# 0831.net
KiCad netlist of a schematic drawn in Altium Designer
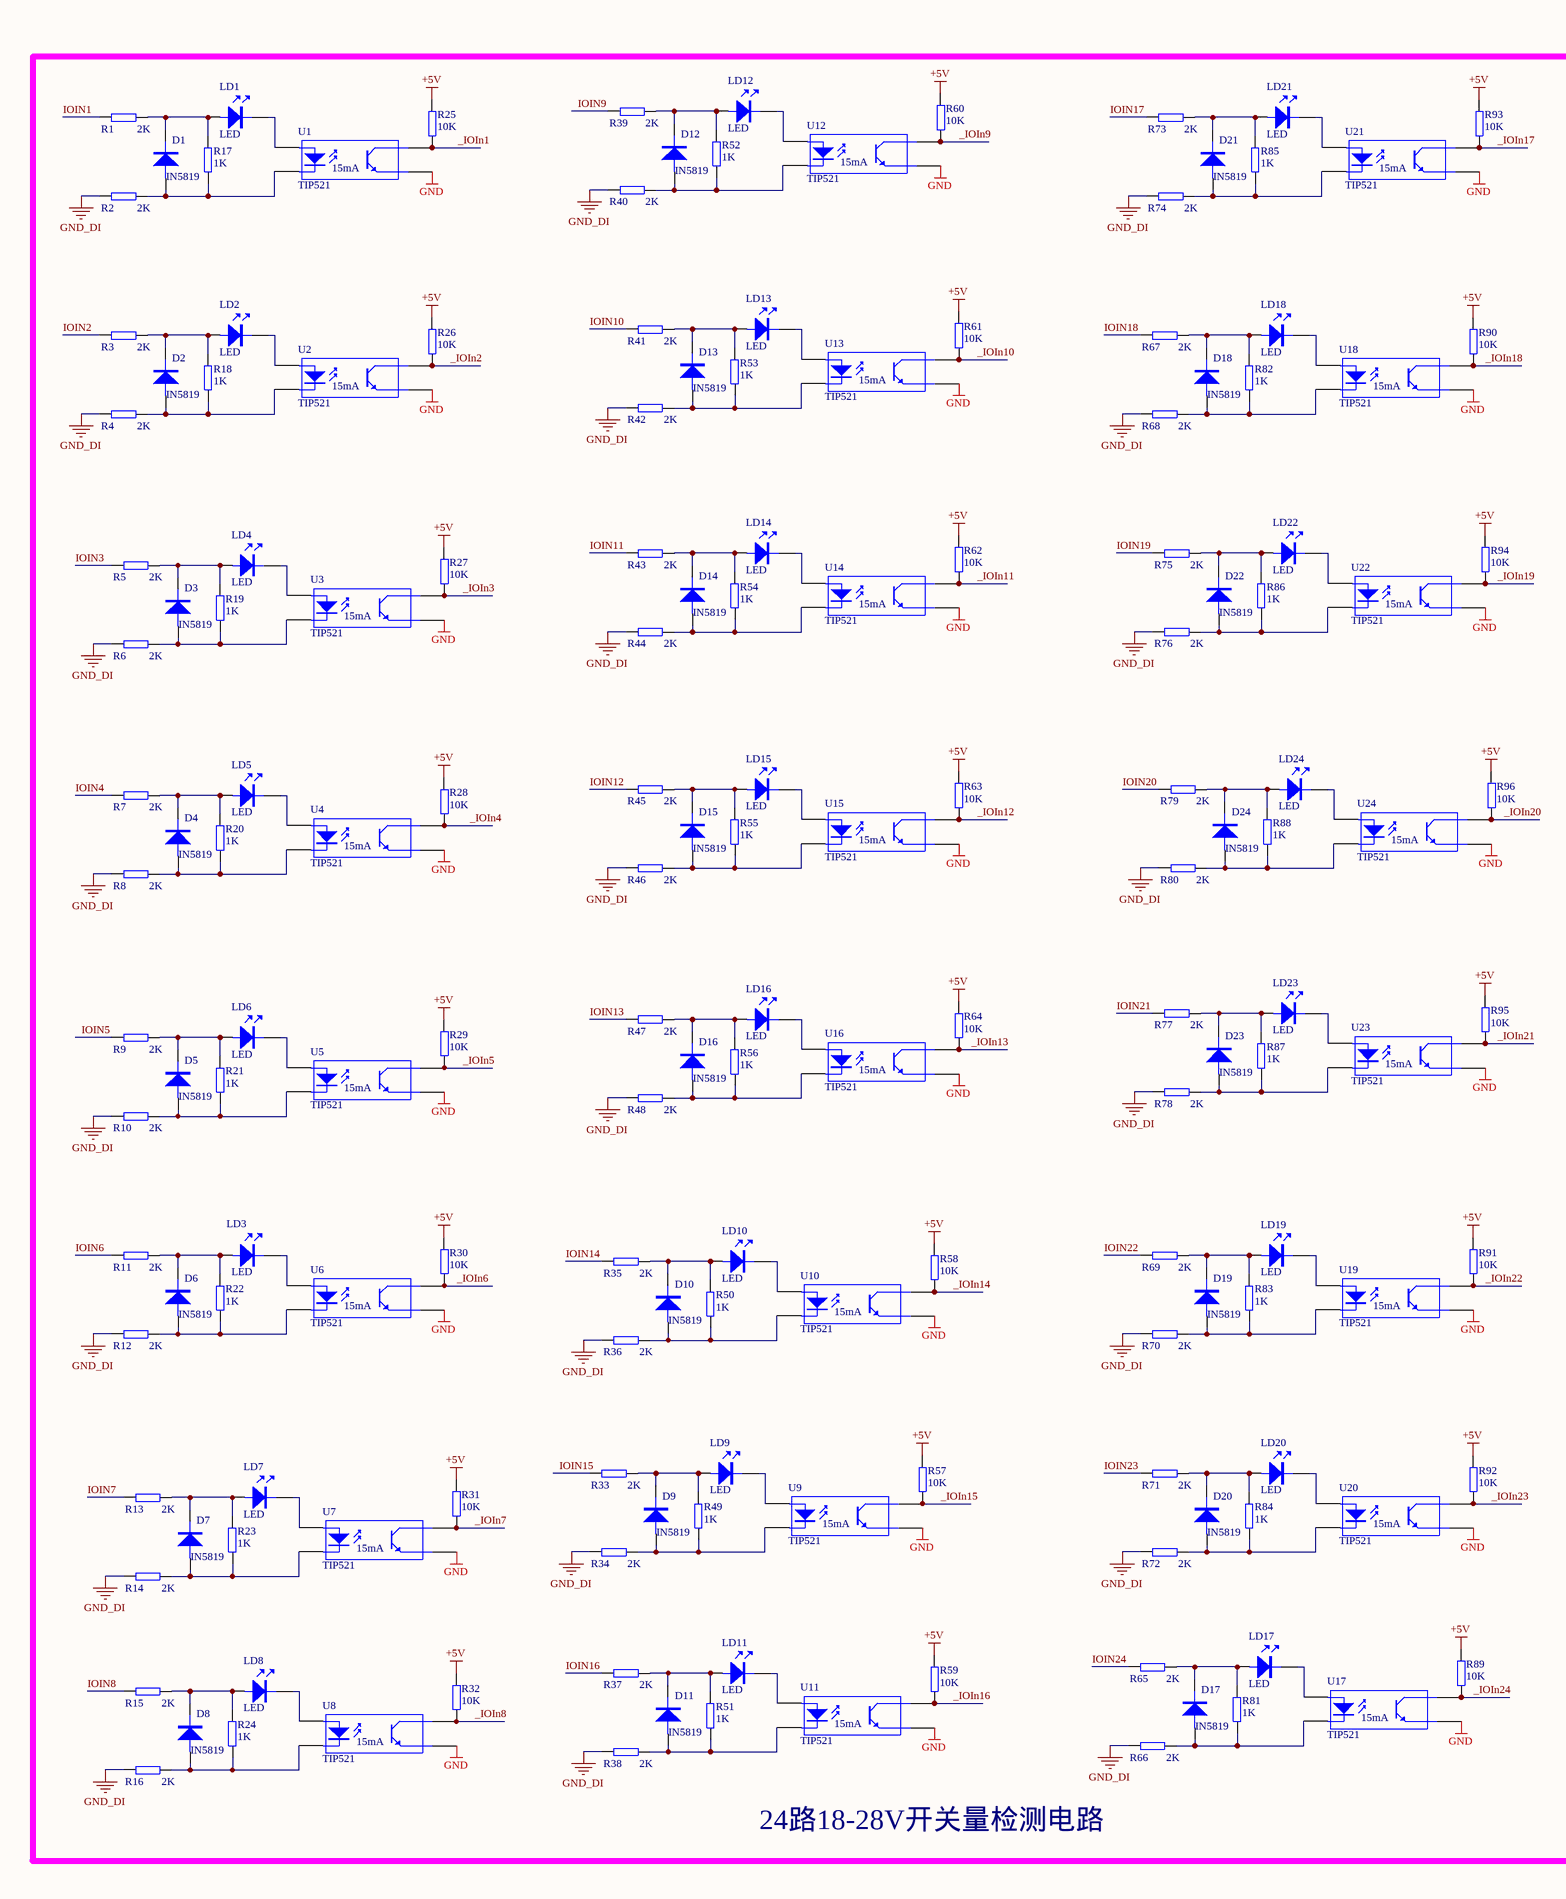
[diagram p0: 如意硬件采集模块0831.SchDoc, left]
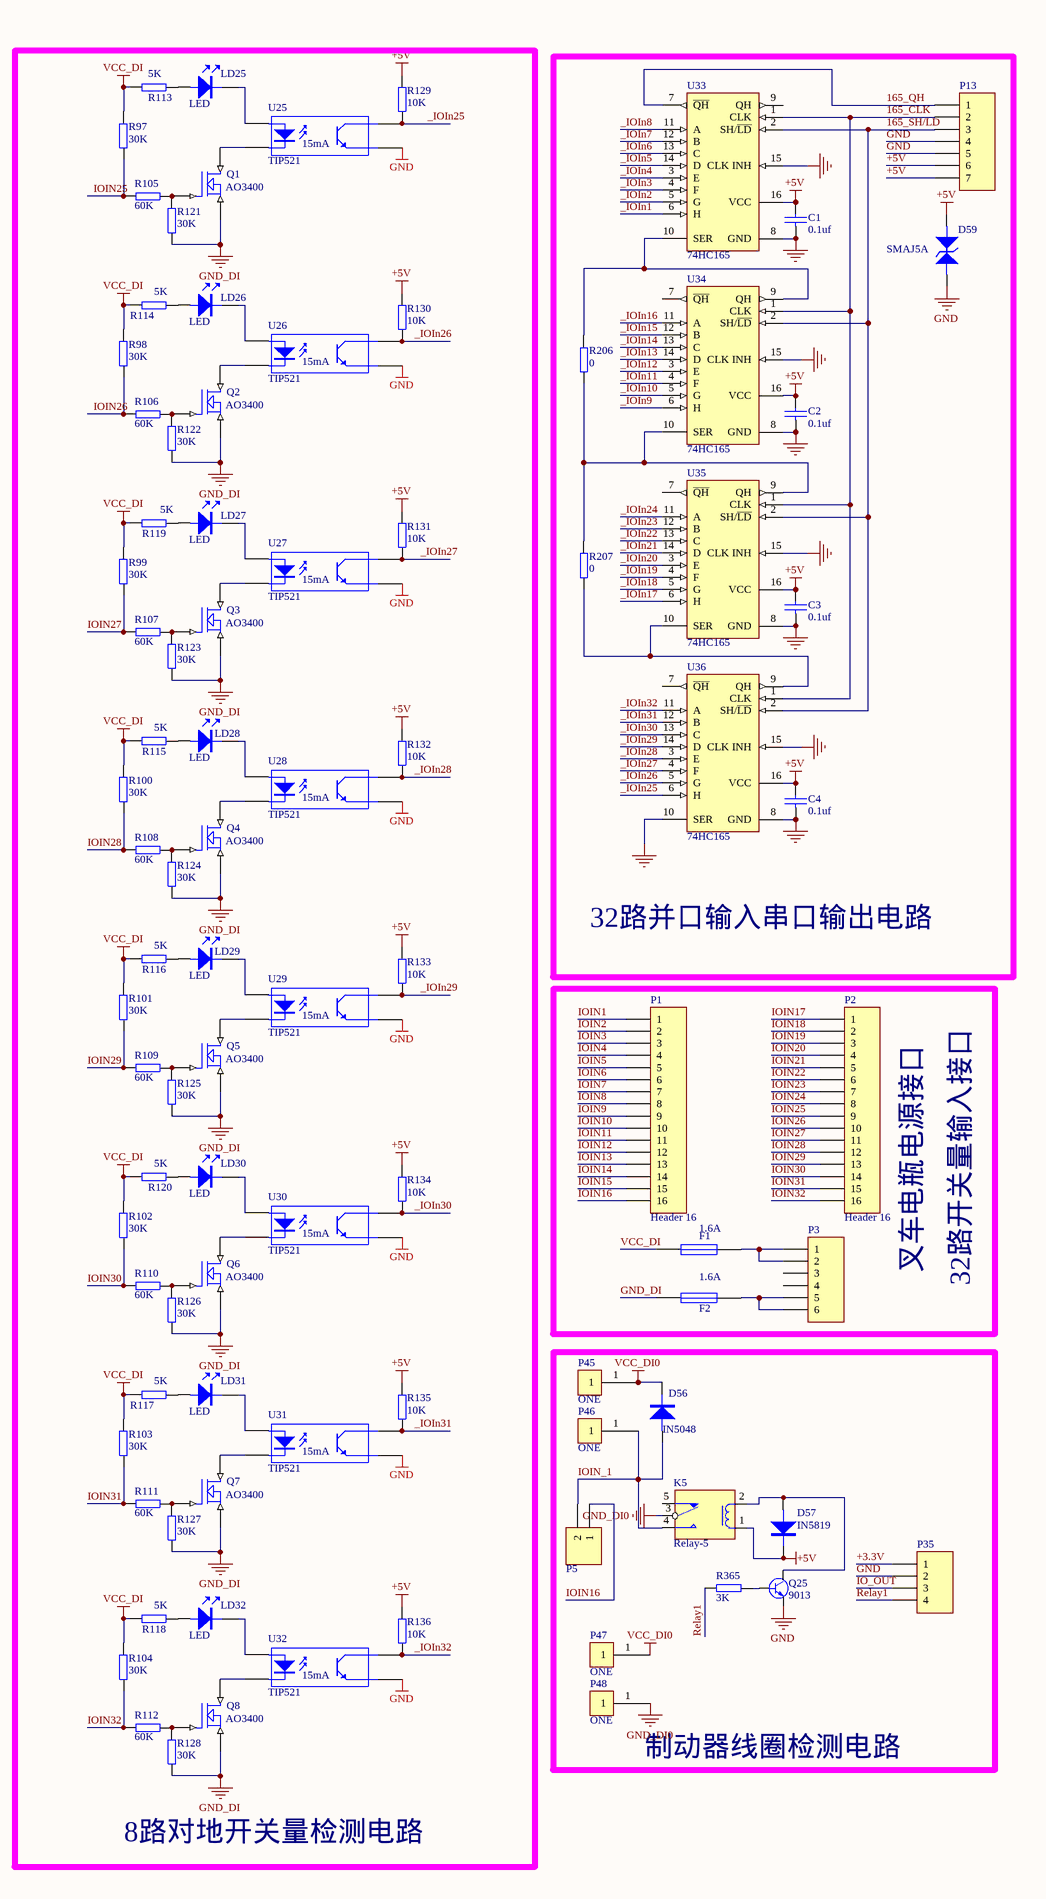
[diagram p1: 如意硬件采集模块0831.SchDoc, right]

(export (version "E")
  (design (tool "Eeschema 10.0.6"))
  (components
    (comp (ref "C1")
      (value "0.1uf")
      (footprint "0603C-1")
      (description "Capacitor")
      (libsource (lib "*") (part "CAP"))
    )
    (comp (ref "C2")
      (value "0.1uf")
      (footprint "0603C-1")
      (description "Capacitor")
      (libsource (lib "*") (part "CAP"))
    )
    (comp (ref "C3")
      (value "0.1uf")
      (footprint "0603C-1")
      (description "Capacitor")
      (libsource (lib "*") (part "CAP"))
    )
    (comp (ref "C4")
      (value "0.1uf")
      (footprint "0603C-1")
      (description "Capacitor")
      (libsource (lib "*") (part "CAP"))
    )
    (comp (ref "D1")
      (value "IN5819")
      (footprint "DIODETP-5")
      (description "Diode")
      (libsource (lib "*") (part "DIODE"))
    )
    (comp (ref "D2")
      (value "IN5819")
      (footprint "DIODETP-5")
      (description "Diode")
      (libsource (lib "*") (part "DIODE"))
    )
    (comp (ref "D3")
      (value "IN5819")
      (footprint "DIODETP-5")
      (description "Diode")
      (libsource (lib "*") (part "DIODE"))
    )
    (comp (ref "D4")
      (value "IN5819")
      (footprint "DIODETP-5")
      (description "Diode")
      (libsource (lib "*") (part "DIODE"))
    )
    (comp (ref "D5")
      (value "IN5819")
      (footprint "DIODETP-5")
      (description "Diode")
      (libsource (lib "*") (part "DIODE"))
    )
    (comp (ref "D6")
      (value "IN5819")
      (footprint "DIODETP-5")
      (description "Diode")
      (libsource (lib "*") (part "DIODE"))
    )
    (comp (ref "D7")
      (value "IN5819")
      (footprint "DIODETP-5")
      (description "Diode")
      (libsource (lib "*") (part "DIODE"))
    )
    (comp (ref "D8")
      (value "IN5819")
      (footprint "DIODETP-5")
      (description "Diode")
      (libsource (lib "*") (part "DIODE"))
    )
    (comp (ref "D9")
      (value "IN5819")
      (footprint "DIODETP-5")
      (description "Diode")
      (libsource (lib "*") (part "DIODE"))
    )
    (comp (ref "D10")
      (value "IN5819")
      (footprint "DIODETP-5")
      (description "Diode")
      (libsource (lib "*") (part "DIODE"))
    )
    (comp (ref "D11")
      (value "IN5819")
      (footprint "DIODETP-5")
      (description "Diode")
      (libsource (lib "*") (part "DIODE"))
    )
    (comp (ref "D12")
      (value "IN5819")
      (footprint "DIODETP-5")
      (description "Diode")
      (libsource (lib "*") (part "DIODE"))
    )
    (comp (ref "D13")
      (value "IN5819")
      (footprint "DIODETP-5")
      (description "Diode")
      (libsource (lib "*") (part "DIODE"))
    )
    (comp (ref "D14")
      (value "IN5819")
      (footprint "DIODETP-5")
      (description "Diode")
      (libsource (lib "*") (part "DIODE"))
    )
    (comp (ref "D15")
      (value "IN5819")
      (footprint "DIODETP-5")
      (description "Diode")
      (libsource (lib "*") (part "DIODE"))
    )
    (comp (ref "D16")
      (value "IN5819")
      (footprint "DIODETP-5")
      (description "Diode")
      (libsource (lib "*") (part "DIODE"))
    )
    (comp (ref "D17")
      (value "IN5819")
      (footprint "DIODETP-5")
      (description "Diode")
      (libsource (lib "*") (part "DIODE"))
    )
    (comp (ref "D18")
      (value "IN5819")
      (footprint "DIODETP-5")
      (description "Diode")
      (libsource (lib "*") (part "DIODE"))
    )
    (comp (ref "D19")
      (value "IN5819")
      (footprint "DIODETP-5")
      (description "Diode")
      (libsource (lib "*") (part "DIODE"))
    )
    (comp (ref "D20")
      (value "IN5819")
      (footprint "DIODETP-5")
      (description "Diode")
      (libsource (lib "*") (part "DIODE"))
    )
    (comp (ref "D21")
      (value "IN5819")
      (footprint "DIODETP-5")
      (description "Diode")
      (libsource (lib "*") (part "DIODE"))
    )
    (comp (ref "D22")
      (value "IN5819")
      (footprint "DIODETP-5")
      (description "Diode")
      (libsource (lib "*") (part "DIODE"))
    )
    (comp (ref "D23")
      (value "IN5819")
      (footprint "DIODETP-5")
      (description "Diode")
      (libsource (lib "*") (part "DIODE"))
    )
    (comp (ref "D24")
      (value "IN5819")
      (footprint "DIODETP-5")
      (description "Diode")
      (libsource (lib "*") (part "DIODE"))
    )
    (comp (ref "D56")
      (value "IN5048")
      (footprint "DIODE-AXL")
      (description "Diode")
      (libsource (lib "*") (part "DIODE"))
    )
    (comp (ref "D57")
      (value "IN5819")
      (footprint "DIODETP-5")
      (description "Diode")
      (libsource (lib "*") (part "DIODE"))
    )
    (comp (ref "D59") (value "SMAJ5A") (footprint "SMB") (libsource (lib "*") (part "TVS")))
    (comp (ref "F1")
      (value "1.6A")
      (footprint "1812")
      (description "Fuse")
      (libsource (lib "*") (part "FUSE1"))
    )
    (comp (ref "F2")
      (value "1.6A")
      (footprint "1812")
      (description "Fuse")
      (libsource (lib "*") (part "FUSE1"))
    )
    (comp (ref "K5") (value "Relay-5") (footprint "RELAYJL") (libsource (lib "zongruyi") (part "Relay-5")))
    (comp (ref "LD1") (value "LED") (footprint "LED_Z1") (libsource (lib "*") (part "LED")))
    (comp (ref "LD2") (value "LED") (footprint "LED_Z1") (libsource (lib "*") (part "LED")))
    (comp (ref "LD3") (value "LED") (footprint "LED_Z1") (libsource (lib "*") (part "LED")))
    (comp (ref "LD4") (value "LED") (footprint "LED_Z1") (libsource (lib "*") (part "LED")))
    (comp (ref "LD5") (value "LED") (footprint "LED_Z1") (libsource (lib "*") (part "LED")))
    (comp (ref "LD6") (value "LED") (footprint "LED_Z1") (libsource (lib "*") (part "LED")))
    (comp (ref "LD7") (value "LED") (footprint "LED_Z1") (libsource (lib "*") (part "LED")))
    (comp (ref "LD8") (value "LED") (footprint "LED_Z1") (libsource (lib "*") (part "LED")))
    (comp (ref "LD9") (value "LED") (footprint "LED_Z1") (libsource (lib "*") (part "LED")))
    (comp (ref "LD10") (value "LED") (footprint "LED_Z1") (libsource (lib "*") (part "LED")))
    (comp (ref "LD11") (value "LED") (footprint "LED_Z1") (libsource (lib "*") (part "LED")))
    (comp (ref "LD12") (value "LED") (footprint "LED_Z1") (libsource (lib "*") (part "LED")))
    (comp (ref "LD13") (value "LED") (footprint "LED_Z1") (libsource (lib "*") (part "LED")))
    (comp (ref "LD14") (value "LED") (footprint "LED_Z1") (libsource (lib "*") (part "LED")))
    (comp (ref "LD15") (value "LED") (footprint "LED_Z1") (libsource (lib "*") (part "LED")))
    (comp (ref "LD16") (value "LED") (footprint "LED_Z1") (libsource (lib "*") (part "LED")))
    (comp (ref "LD17") (value "LED") (footprint "LED_Z1") (libsource (lib "*") (part "LED")))
    (comp (ref "LD18") (value "LED") (footprint "LED_Z1") (libsource (lib "*") (part "LED")))
    (comp (ref "LD19") (value "LED") (footprint "LED_Z1") (libsource (lib "*") (part "LED")))
    (comp (ref "LD20") (value "LED") (footprint "LED_Z1") (libsource (lib "*") (part "LED")))
    (comp (ref "LD21") (value "LED") (footprint "LED_Z1") (libsource (lib "*") (part "LED")))
    (comp (ref "LD22") (value "LED") (footprint "LED_Z1") (libsource (lib "*") (part "LED")))
    (comp (ref "LD23") (value "LED") (footprint "LED_Z1") (libsource (lib "*") (part "LED")))
    (comp (ref "LD24") (value "LED") (footprint "LED_Z1") (libsource (lib "*") (part "LED")))
    (comp (ref "LD25") (value "LED") (footprint "LED_Z1") (libsource (lib "*") (part "LED")))
    (comp (ref "LD26") (value "LED") (footprint "LED_Z1") (libsource (lib "*") (part "LED")))
    (comp (ref "LD27") (value "LED") (footprint "LED_Z1") (libsource (lib "*") (part "LED")))
    (comp (ref "LD28") (value "LED") (footprint "LED_Z1") (libsource (lib "*") (part "LED")))
    (comp (ref "LD29") (value "LED") (footprint "LED_Z1") (libsource (lib "*") (part "LED")))
    (comp (ref "LD30") (value "LED") (footprint "LED_Z1") (libsource (lib "*") (part "LED")))
    (comp (ref "LD31") (value "LED") (footprint "LED_Z1") (libsource (lib "*") (part "LED")))
    (comp (ref "LD32") (value "LED") (footprint "LED_Z1") (libsource (lib "*") (part "LED")))
    (comp (ref "P1")
      (value "Header 16")
      (footprint "KF3.96-16P")
      (description "Header16贴片")
      (fields (field (name "PUBLISHER") "Altium Limited"))
      (libsource (lib "Fszhang") (part "Header 16"))
    )
    (comp (ref "P2")
      (value "Header 16")
      (footprint "KF3.96-16P")
      (description "Header16贴片")
      (fields (field (name "PUBLISHER") "Altium Limited"))
      (libsource (lib "Fszhang") (part "Header 16"))
    )
    (comp (ref "P3")
      (value "Header 6")
      (footprint "HDR1X6")
      (description "Header, 6-Pin")
      (fields (field (name "PUBLISHER") "Altium Limited"))
      (libsource (lib "Miscellaneous Connectors") (part "Header 6"))
    )
    (comp (ref "P5")
      (value "Header 2")
      (footprint "HDR2X1_A")
      (description "接插件")
      (fields (field (name "PUBLISHER") "Altium Limited"))
      (libsource (lib "Fszhang") (part "Header 2"))
    )
    (comp (ref "P13")
      (value "Header 7")
      (footprint "HDR1X7")
      (description "Header, 7-Pin")
      (fields (field (name "PUBLISHER") "Altium Limited"))
      (libsource (lib "Miscellaneous Connectors") (part "Header 7"))
    )
    (comp (ref "P35")
      (value "Header 4")
      (footprint "HDR1X4")
      (description "Header, 4-Pin")
      (fields (field (name "PUBLISHER") "Altium Limited"))
      (libsource (lib "Miscellaneous Connectors") (part "Header 4"))
    )
    (comp (ref "P45") (value "ONE") (footprint "ONE") (libsource (lib "zongruyi") (part "ONE")))
    (comp (ref "P46") (value "ONE") (footprint "ONE") (libsource (lib "zongruyi") (part "ONE")))
    (comp (ref "P47") (value "ONE") (footprint "ONE") (libsource (lib "zongruyi") (part "ONE")))
    (comp (ref "P48") (value "ONE") (footprint "ONE") (libsource (lib "zongruyi") (part "ONE")))
    (comp (ref "Q1") (value "AO3400") (footprint "SOT23-JFET") (libsource (lib "*") (part "MOSFET N")))
    (comp (ref "Q2") (value "AO3400") (footprint "SOT23-JFET") (libsource (lib "*") (part "MOSFET N")))
    (comp (ref "Q3") (value "AO3400") (footprint "SOT23-JFET") (libsource (lib "*") (part "MOSFET N")))
    (comp (ref "Q4") (value "AO3400") (footprint "SOT23-JFET") (libsource (lib "*") (part "MOSFET N")))
    (comp (ref "Q5") (value "AO3400") (footprint "SOT23-JFET") (libsource (lib "*") (part "MOSFET N")))
    (comp (ref "Q6") (value "AO3400") (footprint "SOT23-JFET") (libsource (lib "*") (part "MOSFET N")))
    (comp (ref "Q7") (value "AO3400") (footprint "SOT23-JFET") (libsource (lib "*") (part "MOSFET N")))
    (comp (ref "Q8") (value "AO3400") (footprint "SOT23-JFET") (libsource (lib "*") (part "MOSFET N")))
    (comp (ref "Q25") (value "9013") (footprint "SOT23-BCE") (libsource (lib "*") (part "NPN")))
    (comp (ref "R1") (value "2K") (footprint "0603R-1") (libsource (lib "*") (part "RES2")))
    (comp (ref "R2") (value "2K") (footprint "0603R-1") (libsource (lib "*") (part "RES2")))
    (comp (ref "R3") (value "2K") (footprint "0603R-1") (libsource (lib "*") (part "RES2")))
    (comp (ref "R4") (value "2K") (footprint "0603R-1") (libsource (lib "*") (part "RES2")))
    (comp (ref "R5") (value "2K") (footprint "0603R-1") (libsource (lib "*") (part "RES2")))
    (comp (ref "R6") (value "2K") (footprint "0603R-1") (libsource (lib "*") (part "RES2")))
    (comp (ref "R7") (value "2K") (footprint "0603R-1") (libsource (lib "*") (part "RES2")))
    (comp (ref "R8") (value "2K") (footprint "0603R-1") (libsource (lib "*") (part "RES2")))
    (comp (ref "R9") (value "2K") (footprint "0603R-1") (libsource (lib "*") (part "RES2")))
    (comp (ref "R10") (value "2K") (footprint "0603R-1") (libsource (lib "*") (part "RES2")))
    (comp (ref "R11") (value "2K") (footprint "0603R-1") (libsource (lib "*") (part "RES2")))
    (comp (ref "R12") (value "2K") (footprint "0603R-1") (libsource (lib "*") (part "RES2")))
    (comp (ref "R13") (value "2K") (footprint "0603R-1") (libsource (lib "*") (part "RES2")))
    (comp (ref "R14") (value "2K") (footprint "0603R-1") (libsource (lib "*") (part "RES2")))
    (comp (ref "R15") (value "2K") (footprint "0603R-1") (libsource (lib "*") (part "RES2")))
    (comp (ref "R16") (value "2K") (footprint "0603R-1") (libsource (lib "*") (part "RES2")))
    (comp (ref "R17") (value "1K") (footprint "0603R-1") (libsource (lib "*") (part "RES2")))
    (comp (ref "R18") (value "1K") (footprint "0603R-1") (libsource (lib "*") (part "RES2")))
    (comp (ref "R19") (value "1K") (footprint "0603R-1") (libsource (lib "*") (part "RES2")))
    (comp (ref "R20") (value "1K") (footprint "0603R-1") (libsource (lib "*") (part "RES2")))
    (comp (ref "R21") (value "1K") (footprint "0603R-1") (libsource (lib "*") (part "RES2")))
    (comp (ref "R22") (value "1K") (footprint "0603R-1") (libsource (lib "*") (part "RES2")))
    (comp (ref "R23") (value "1K") (footprint "0603R-1") (libsource (lib "*") (part "RES2")))
    (comp (ref "R24") (value "1K") (footprint "0603R-1") (libsource (lib "*") (part "RES2")))
    (comp (ref "R25") (value "10K") (footprint "0603R-1") (libsource (lib "*") (part "RES2")))
    (comp (ref "R26") (value "10K") (footprint "0603R-1") (libsource (lib "*") (part "RES2")))
    (comp (ref "R27") (value "10K") (footprint "0603R-1") (libsource (lib "*") (part "RES2")))
    (comp (ref "R28") (value "10K") (footprint "0603R-1") (libsource (lib "*") (part "RES2")))
    (comp (ref "R29") (value "10K") (footprint "0603R-1") (libsource (lib "*") (part "RES2")))
    (comp (ref "R30") (value "10K") (footprint "0603R-1") (libsource (lib "*") (part "RES2")))
    (comp (ref "R31") (value "10K") (footprint "0603R-1") (libsource (lib "*") (part "RES2")))
    (comp (ref "R32") (value "10K") (footprint "0603R-1") (libsource (lib "*") (part "RES2")))
    (comp (ref "R33") (value "2K") (footprint "0603R-1") (libsource (lib "*") (part "RES2")))
    (comp (ref "R34") (value "2K") (footprint "0603R-1") (libsource (lib "*") (part "RES2")))
    (comp (ref "R35") (value "2K") (footprint "0603R-1") (libsource (lib "*") (part "RES2")))
    (comp (ref "R36") (value "2K") (footprint "0603R-1") (libsource (lib "*") (part "RES2")))
    (comp (ref "R37") (value "2K") (footprint "0603R-1") (libsource (lib "*") (part "RES2")))
    (comp (ref "R38") (value "2K") (footprint "0603R-1") (libsource (lib "*") (part "RES2")))
    (comp (ref "R39") (value "2K") (footprint "0603R-1") (libsource (lib "*") (part "RES2")))
    (comp (ref "R40") (value "2K") (footprint "0603R-1") (libsource (lib "*") (part "RES2")))
    (comp (ref "R41") (value "2K") (footprint "0603R-1") (libsource (lib "*") (part "RES2")))
    (comp (ref "R42") (value "2K") (footprint "0603R-1") (libsource (lib "*") (part "RES2")))
    (comp (ref "R43") (value "2K") (footprint "0603R-1") (libsource (lib "*") (part "RES2")))
    (comp (ref "R44") (value "2K") (footprint "0603R-1") (libsource (lib "*") (part "RES2")))
    (comp (ref "R45") (value "2K") (footprint "0603R-1") (libsource (lib "*") (part "RES2")))
    (comp (ref "R46") (value "2K") (footprint "0603R-1") (libsource (lib "*") (part "RES2")))
    (comp (ref "R47") (value "2K") (footprint "0603R-1") (libsource (lib "*") (part "RES2")))
    (comp (ref "R48") (value "2K") (footprint "0603R-1") (libsource (lib "*") (part "RES2")))
    (comp (ref "R49") (value "1K") (footprint "0603R-1") (libsource (lib "*") (part "RES2")))
    (comp (ref "R50") (value "1K") (footprint "0603R-1") (libsource (lib "*") (part "RES2")))
    (comp (ref "R51") (value "1K") (footprint "0603R-1") (libsource (lib "*") (part "RES2")))
    (comp (ref "R52") (value "1K") (footprint "0603R-1") (libsource (lib "*") (part "RES2")))
    (comp (ref "R53") (value "1K") (footprint "0603R-1") (libsource (lib "*") (part "RES2")))
    (comp (ref "R54") (value "1K") (footprint "0603R-1") (libsource (lib "*") (part "RES2")))
    (comp (ref "R55") (value "1K") (footprint "0603R-1") (libsource (lib "*") (part "RES2")))
    (comp (ref "R56") (value "1K") (footprint "0603R-1") (libsource (lib "*") (part "RES2")))
    (comp (ref "R57") (value "10K") (footprint "0603R-1") (libsource (lib "*") (part "RES2")))
    (comp (ref "R58") (value "10K") (footprint "0603R-1") (libsource (lib "*") (part "RES2")))
    (comp (ref "R59") (value "10K") (footprint "0603R-1") (libsource (lib "*") (part "RES2")))
    (comp (ref "R60") (value "10K") (footprint "0603R-1") (libsource (lib "*") (part "RES2")))
    (comp (ref "R61") (value "10K") (footprint "0603R-1") (libsource (lib "*") (part "RES2")))
    (comp (ref "R62") (value "10K") (footprint "0603R-1") (libsource (lib "*") (part "RES2")))
    (comp (ref "R63") (value "10K") (footprint "0603R-1") (libsource (lib "*") (part "RES2")))
    (comp (ref "R64") (value "10K") (footprint "0603R-1") (libsource (lib "*") (part "RES2")))
    (comp (ref "R65") (value "2K") (footprint "0603R-1") (libsource (lib "*") (part "RES2")))
    (comp (ref "R66") (value "2K") (footprint "0603R-1") (libsource (lib "*") (part "RES2")))
    (comp (ref "R67") (value "2K") (footprint "0603R-1") (libsource (lib "*") (part "RES2")))
    (comp (ref "R68") (value "2K") (footprint "0603R-1") (libsource (lib "*") (part "RES2")))
    (comp (ref "R69") (value "2K") (footprint "0603R-1") (libsource (lib "*") (part "RES2")))
    (comp (ref "R70") (value "2K") (footprint "0603R-1") (libsource (lib "*") (part "RES2")))
    (comp (ref "R71") (value "2K") (footprint "0603R-1") (libsource (lib "*") (part "RES2")))
    (comp (ref "R72") (value "2K") (footprint "0603R-1") (libsource (lib "*") (part "RES2")))
    (comp (ref "R73") (value "2K") (footprint "0603R-1") (libsource (lib "*") (part "RES2")))
    (comp (ref "R74") (value "2K") (footprint "0603R-1") (libsource (lib "*") (part "RES2")))
    (comp (ref "R75") (value "2K") (footprint "0603R-1") (libsource (lib "*") (part "RES2")))
    (comp (ref "R76") (value "2K") (footprint "0603R-1") (libsource (lib "*") (part "RES2")))
    (comp (ref "R77") (value "2K") (footprint "0603R-1") (libsource (lib "*") (part "RES2")))
    (comp (ref "R78") (value "2K") (footprint "0603R-1") (libsource (lib "*") (part "RES2")))
    (comp (ref "R79") (value "2K") (footprint "0603R-1") (libsource (lib "*") (part "RES2")))
    (comp (ref "R80") (value "2K") (footprint "0603R-1") (libsource (lib "*") (part "RES2")))
    (comp (ref "R81") (value "1K") (footprint "0603R-1") (libsource (lib "*") (part "RES2")))
    (comp (ref "R82") (value "1K") (footprint "0603R-1") (libsource (lib "*") (part "RES2")))
    (comp (ref "R83") (value "1K") (footprint "0603R-1") (libsource (lib "*") (part "RES2")))
    (comp (ref "R84") (value "1K") (footprint "0603R-1") (libsource (lib "*") (part "RES2")))
    (comp (ref "R85") (value "1K") (footprint "0603R-1") (libsource (lib "*") (part "RES2")))
    (comp (ref "R86") (value "1K") (footprint "0603R-1") (libsource (lib "*") (part "RES2")))
    (comp (ref "R87") (value "1K") (footprint "0603R-1") (libsource (lib "*") (part "RES2")))
    (comp (ref "R88") (value "1K") (footprint "0603R-1") (libsource (lib "*") (part "RES2")))
    (comp (ref "R89") (value "10K") (footprint "0603R-1") (libsource (lib "*") (part "RES2")))
    (comp (ref "R90") (value "10K") (footprint "0603R-1") (libsource (lib "*") (part "RES2")))
    (comp (ref "R91") (value "10K") (footprint "0603R-1") (libsource (lib "*") (part "RES2")))
    (comp (ref "R92") (value "10K") (footprint "0603R-1") (libsource (lib "*") (part "RES2")))
    (comp (ref "R93") (value "10K") (footprint "0603R-1") (libsource (lib "*") (part "RES2")))
    (comp (ref "R94") (value "10K") (footprint "0603R-1") (libsource (lib "*") (part "RES2")))
    (comp (ref "R95") (value "10K") (footprint "0603R-1") (libsource (lib "*") (part "RES2")))
    (comp (ref "R96") (value "10K") (footprint "0603R-1") (libsource (lib "*") (part "RES2")))
    (comp (ref "R97") (value "30K") (footprint "0603R-1") (libsource (lib "*") (part "RES2")))
    (comp (ref "R98") (value "30K") (footprint "0603R-1") (libsource (lib "*") (part "RES2")))
    (comp (ref "R99") (value "30K") (footprint "0603R-1") (libsource (lib "*") (part "RES2")))
    (comp (ref "R100") (value "30K") (footprint "0603R-1") (libsource (lib "*") (part "RES2")))
    (comp (ref "R101") (value "30K") (footprint "0603R-1") (libsource (lib "*") (part "RES2")))
    (comp (ref "R102") (value "30K") (footprint "0603R-1") (libsource (lib "*") (part "RES2")))
    (comp (ref "R103") (value "30K") (footprint "0603R-1") (libsource (lib "*") (part "RES2")))
    (comp (ref "R104") (value "30K") (footprint "0603R-1") (libsource (lib "*") (part "RES2")))
    (comp (ref "R105") (value "60K") (footprint "0603R-1") (libsource (lib "*") (part "RES-2")))
    (comp (ref "R106") (value "60K") (footprint "0603R-1") (libsource (lib "*") (part "RES-2")))
    (comp (ref "R107") (value "60K") (footprint "0603R-1") (libsource (lib "*") (part "RES-2")))
    (comp (ref "R108") (value "60K") (footprint "0603R-1") (libsource (lib "*") (part "RES-2")))
    (comp (ref "R109") (value "60K") (footprint "0603R-1") (libsource (lib "*") (part "RES-2")))
    (comp (ref "R110") (value "60K") (footprint "0603R-1") (libsource (lib "*") (part "RES-2")))
    (comp (ref "R111") (value "60K") (footprint "0603R-1") (libsource (lib "*") (part "RES-2")))
    (comp (ref "R112") (value "60K") (footprint "0603R-1") (libsource (lib "*") (part "RES-2")))
    (comp (ref "R113") (value "5K") (footprint "0603R-1") (libsource (lib "*") (part "RES2")))
    (comp (ref "R114") (value "5K") (footprint "0603R-1") (libsource (lib "*") (part "RES2")))
    (comp (ref "R115") (value "5K") (footprint "0603R-1") (libsource (lib "*") (part "RES2")))
    (comp (ref "R116") (value "5K") (footprint "0603R-1") (libsource (lib "*") (part "RES2")))
    (comp (ref "R117") (value "5K") (footprint "0603R-1") (libsource (lib "*") (part "RES2")))
    (comp (ref "R118") (value "5K") (footprint "0603R-1") (libsource (lib "*") (part "RES2")))
    (comp (ref "R119") (value "5K") (footprint "0603R-1") (libsource (lib "*") (part "RES2")))
    (comp (ref "R120") (value "5K") (footprint "0603R-1") (libsource (lib "*") (part "RES2")))
    (comp (ref "R121") (value "30K") (footprint "0603R-1") (libsource (lib "*") (part "RES-2")))
    (comp (ref "R122") (value "30K") (footprint "0603R-1") (libsource (lib "*") (part "RES-2")))
    (comp (ref "R123") (value "30K") (footprint "0603R-1") (libsource (lib "*") (part "RES-2")))
    (comp (ref "R124") (value "30K") (footprint "0603R-1") (libsource (lib "*") (part "RES-2")))
    (comp (ref "R125") (value "30K") (footprint "0603R-1") (libsource (lib "*") (part "RES-2")))
    (comp (ref "R126") (value "30K") (footprint "0603R-1") (libsource (lib "*") (part "RES-2")))
    (comp (ref "R127") (value "30K") (footprint "0603R-1") (libsource (lib "*") (part "RES-2")))
    (comp (ref "R128") (value "30K") (footprint "0603R-1") (libsource (lib "*") (part "RES-2")))
    (comp (ref "R129") (value "10K") (footprint "0603R-1") (libsource (lib "*") (part "RES2")))
    (comp (ref "R130") (value "10K") (footprint "0603R-1") (libsource (lib "*") (part "RES2")))
    (comp (ref "R131") (value "10K") (footprint "0603R-1") (libsource (lib "*") (part "RES2")))
    (comp (ref "R132") (value "10K") (footprint "0603R-1") (libsource (lib "*") (part "RES2")))
    (comp (ref "R133") (value "10K") (footprint "0603R-1") (libsource (lib "*") (part "RES2")))
    (comp (ref "R134") (value "10K") (footprint "0603R-1") (libsource (lib "*") (part "RES2")))
    (comp (ref "R135") (value "10K") (footprint "0603R-1") (libsource (lib "*") (part "RES2")))
    (comp (ref "R136") (value "10K") (footprint "0603R-1") (libsource (lib "*") (part "RES2")))
    (comp (ref "R206") (value "0") (footprint "0603R-1") (libsource (lib "*") (part "RES2")))
    (comp (ref "R207") (value "0") (footprint "0603R-1") (libsource (lib "*") (part "RES2")))
    (comp (ref "R365") (value "3K") (footprint "0603R-1") (libsource (lib "*") (part "RES-2")))
    (comp (ref "U1")
      (value "TIP521")
      (footprint "DIP-4")
      (description "Optoisolator")
      (libsource (lib "*") (part "OPTOISO1"))
    )
    (comp (ref "U2")
      (value "TIP521")
      (footprint "DIP-4")
      (description "Optoisolator")
      (libsource (lib "*") (part "OPTOISO1"))
    )
    (comp (ref "U3")
      (value "TIP521")
      (footprint "DIP-4")
      (description "Optoisolator")
      (libsource (lib "*") (part "OPTOISO1"))
    )
    (comp (ref "U4")
      (value "TIP521")
      (footprint "DIP-4")
      (description "Optoisolator")
      (libsource (lib "*") (part "OPTOISO1"))
    )
    (comp (ref "U5")
      (value "TIP521")
      (footprint "DIP-4")
      (description "Optoisolator")
      (libsource (lib "*") (part "OPTOISO1"))
    )
    (comp (ref "U6")
      (value "TIP521")
      (footprint "DIP-4")
      (description "Optoisolator")
      (libsource (lib "*") (part "OPTOISO1"))
    )
    (comp (ref "U7")
      (value "TIP521")
      (footprint "DIP-4")
      (description "Optoisolator")
      (libsource (lib "*") (part "OPTOISO1"))
    )
    (comp (ref "U8")
      (value "TIP521")
      (footprint "DIP-4")
      (description "Optoisolator")
      (libsource (lib "*") (part "OPTOISO1"))
    )
    (comp (ref "U9")
      (value "TIP521")
      (footprint "DIP-4")
      (description "Optoisolator")
      (libsource (lib "*") (part "OPTOISO1"))
    )
    (comp (ref "U10")
      (value "TIP521")
      (footprint "DIP-4")
      (description "Optoisolator")
      (libsource (lib "*") (part "OPTOISO1"))
    )
    (comp (ref "U11")
      (value "TIP521")
      (footprint "DIP-4")
      (description "Optoisolator")
      (libsource (lib "*") (part "OPTOISO1"))
    )
    (comp (ref "U12")
      (value "TIP521")
      (footprint "DIP-4")
      (description "Optoisolator")
      (libsource (lib "*") (part "OPTOISO1"))
    )
    (comp (ref "U13")
      (value "TIP521")
      (footprint "DIP-4")
      (description "Optoisolator")
      (libsource (lib "*") (part "OPTOISO1"))
    )
    (comp (ref "U14")
      (value "TIP521")
      (footprint "DIP-4")
      (description "Optoisolator")
      (libsource (lib "*") (part "OPTOISO1"))
    )
    (comp (ref "U15")
      (value "TIP521")
      (footprint "DIP-4")
      (description "Optoisolator")
      (libsource (lib "*") (part "OPTOISO1"))
    )
    (comp (ref "U16")
      (value "TIP521")
      (footprint "DIP-4")
      (description "Optoisolator")
      (libsource (lib "*") (part "OPTOISO1"))
    )
    (comp (ref "U17")
      (value "TIP521")
      (footprint "DIP-4")
      (description "Optoisolator")
      (libsource (lib "*") (part "OPTOISO1"))
    )
    (comp (ref "U18")
      (value "TIP521")
      (footprint "DIP-4")
      (description "Optoisolator")
      (libsource (lib "*") (part "OPTOISO1"))
    )
    (comp (ref "U19")
      (value "TIP521")
      (footprint "DIP-4")
      (description "Optoisolator")
      (libsource (lib "*") (part "OPTOISO1"))
    )
    (comp (ref "U20")
      (value "TIP521")
      (footprint "DIP-4")
      (description "Optoisolator")
      (libsource (lib "*") (part "OPTOISO1"))
    )
    (comp (ref "U21")
      (value "TIP521")
      (footprint "DIP-4")
      (description "Optoisolator")
      (libsource (lib "*") (part "OPTOISO1"))
    )
    (comp (ref "U22")
      (value "TIP521")
      (footprint "DIP-4")
      (description "Optoisolator")
      (libsource (lib "*") (part "OPTOISO1"))
    )
    (comp (ref "U23")
      (value "TIP521")
      (footprint "DIP-4")
      (description "Optoisolator")
      (libsource (lib "*") (part "OPTOISO1"))
    )
    (comp (ref "U24")
      (value "TIP521")
      (footprint "DIP-4")
      (description "Optoisolator")
      (libsource (lib "*") (part "OPTOISO1"))
    )
    (comp (ref "U25")
      (value "TIP521")
      (footprint "DIP-4")
      (description "Optoisolator")
      (libsource (lib "*") (part "OPTOISO1"))
    )
    (comp (ref "U26")
      (value "TIP521")
      (footprint "DIP-4")
      (description "Optoisolator")
      (libsource (lib "*") (part "OPTOISO1"))
    )
    (comp (ref "U27")
      (value "TIP521")
      (footprint "DIP-4")
      (description "Optoisolator")
      (libsource (lib "*") (part "OPTOISO1"))
    )
    (comp (ref "U28")
      (value "TIP521")
      (footprint "DIP-4")
      (description "Optoisolator")
      (libsource (lib "*") (part "OPTOISO1"))
    )
    (comp (ref "U29")
      (value "TIP521")
      (footprint "DIP-4")
      (description "Optoisolator")
      (libsource (lib "*") (part "OPTOISO1"))
    )
    (comp (ref "U30")
      (value "TIP521")
      (footprint "DIP-4")
      (description "Optoisolator")
      (libsource (lib "*") (part "OPTOISO1"))
    )
    (comp (ref "U31")
      (value "TIP521")
      (footprint "DIP-4")
      (description "Optoisolator")
      (libsource (lib "*") (part "OPTOISO1"))
    )
    (comp (ref "U32")
      (value "TIP521")
      (footprint "DIP-4")
      (description "Optoisolator")
      (libsource (lib "*") (part "OPTOISO1"))
    )
    (comp (ref "U33")
      (value "74HC165")
      (footprint "DIP-16")
      (description "8并口输入，串口输出")
      (fields (field (name "PUBLISHER") "Altium Limited"))
      (libsource (lib "zongruyi") (part "74HC165"))
    )
    (comp (ref "U34")
      (value "74HC165")
      (footprint "DIP-16")
      (description "8并口输入，串口输出")
      (fields (field (name "PUBLISHER") "Altium Limited"))
      (libsource (lib "zongruyi") (part "74HC165"))
    )
    (comp (ref "U35")
      (value "74HC165")
      (footprint "DIP-16")
      (description "8并口输入，串口输出")
      (fields (field (name "PUBLISHER") "Altium Limited"))
      (libsource (lib "zongruyi") (part "74HC165"))
    )
    (comp (ref "U36")
      (value "74HC165")
      (footprint "DIP-16")
      (description "8并口输入，串口输出")
      (fields (field (name "PUBLISHER") "Altium Limited"))
      (libsource (lib "zongruyi") (part "74HC165"))
    )
  )
  (nets
    (net (code "1") (name "+5V") (class "Default")
      (node (ref "C1") (pin "2") (pinfunction "2_2") (pintype "passive"))
      (node (ref "C2") (pin "2") (pinfunction "2_2") (pintype "passive"))
      (node (ref "C3") (pin "2") (pinfunction "2_2") (pintype "passive"))
      (node (ref "C4") (pin "2") (pinfunction "2_2") (pintype "passive"))
      (node (ref "D57") (pin "2") (pinfunction "K_2") (pintype "passive"))
      (node (ref "D59") (pin "2") (pinfunction "K_2") (pintype "passive"))
      (node (ref "K5") (pin "1") (pinfunction "1_1") (pintype "passive"))
      (node (ref "P13") (pin "6") (pinfunction "6_6") (pintype "passive"))
      (node (ref "P13") (pin "7") (pinfunction "7_7") (pintype "passive"))
      (node (ref "R129") (pin "1") (pinfunction "1_1") (pintype "passive"))
      (node (ref "R130") (pin "1") (pinfunction "1_1") (pintype "passive"))
      (node (ref "R131") (pin "1") (pinfunction "1_1") (pintype "passive"))
      (node (ref "R132") (pin "1") (pinfunction "1_1") (pintype "passive"))
      (node (ref "R133") (pin "1") (pinfunction "1_1") (pintype "passive"))
      (node (ref "R134") (pin "1") (pinfunction "1_1") (pintype "passive"))
      (node (ref "R135") (pin "1") (pinfunction "1_1") (pintype "passive"))
      (node (ref "R136") (pin "1") (pinfunction "1_1") (pintype "passive"))
      (node (ref "R25") (pin "1") (pinfunction "1_1") (pintype "passive"))
      (node (ref "R26") (pin "1") (pinfunction "1_1") (pintype "passive"))
      (node (ref "R27") (pin "1") (pinfunction "1_1") (pintype "passive"))
      (node (ref "R28") (pin "1") (pinfunction "1_1") (pintype "passive"))
      (node (ref "R29") (pin "1") (pinfunction "1_1") (pintype "passive"))
      (node (ref "R30") (pin "1") (pinfunction "1_1") (pintype "passive"))
      (node (ref "R31") (pin "1") (pinfunction "1_1") (pintype "passive"))
      (node (ref "R32") (pin "1") (pinfunction "1_1") (pintype "passive"))
      (node (ref "R57") (pin "1") (pinfunction "1_1") (pintype "passive"))
      (node (ref "R58") (pin "1") (pinfunction "1_1") (pintype "passive"))
      (node (ref "R59") (pin "1") (pinfunction "1_1") (pintype "passive"))
      (node (ref "R60") (pin "1") (pinfunction "1_1") (pintype "passive"))
      (node (ref "R61") (pin "1") (pinfunction "1_1") (pintype "passive"))
      (node (ref "R62") (pin "1") (pinfunction "1_1") (pintype "passive"))
      (node (ref "R63") (pin "1") (pinfunction "1_1") (pintype "passive"))
      (node (ref "R64") (pin "1") (pinfunction "1_1") (pintype "passive"))
      (node (ref "R89") (pin "1") (pinfunction "1_1") (pintype "passive"))
      (node (ref "R90") (pin "1") (pinfunction "1_1") (pintype "passive"))
      (node (ref "R91") (pin "1") (pinfunction "1_1") (pintype "passive"))
      (node (ref "R92") (pin "1") (pinfunction "1_1") (pintype "passive"))
      (node (ref "R93") (pin "1") (pinfunction "1_1") (pintype "passive"))
      (node (ref "R94") (pin "1") (pinfunction "1_1") (pintype "passive"))
      (node (ref "R95") (pin "1") (pinfunction "1_1") (pintype "passive"))
      (node (ref "R96") (pin "1") (pinfunction "1_1") (pintype "passive"))
      (node (ref "U33") (pin "16") (pinfunction "VCC_16") (pintype "power_in"))
      (node (ref "U34") (pin "16") (pinfunction "VCC_16") (pintype "power_in"))
      (node (ref "U35") (pin "16") (pinfunction "VCC_16") (pintype "power_in"))
      (node (ref "U36") (pin "16") (pinfunction "VCC_16") (pintype "power_in"))
    )
    (net (code "2") (name "/+3.3V") (class "Default")
      (node (ref "P35") (pin "1") (pinfunction "1_1") (pintype "passive"))
    )
    (net (code "3") (name "/165_CLK") (class "Default")
      (node (ref "P13") (pin "2") (pinfunction "2_2") (pintype "passive"))
      (node (ref "U33") (pin "1") (pinfunction "CLK_1") (pintype "input"))
      (node (ref "U34") (pin "1") (pinfunction "CLK_1") (pintype "input"))
      (node (ref "U35") (pin "1") (pinfunction "CLK_1") (pintype "input"))
      (node (ref "U36") (pin "1") (pinfunction "CLK_1") (pintype "input"))
    )
    (net (code "4") (name "/165_QH") (class "Default")
      (node (ref "P13") (pin "1") (pinfunction "1_1") (pintype "passive"))
      (node (ref "U33") (pin "7") (pinfunction "~{QH}_7") (pintype "output"))
    )
    (net (code "5") (name "/165_SH{slash}LD") (class "Default")
      (node (ref "P13") (pin "3") (pinfunction "3_3") (pintype "passive"))
      (node (ref "U33") (pin "2") (pinfunction "SH/~{LD}_2") (pintype "input"))
      (node (ref "U34") (pin "2") (pinfunction "SH/~{LD}_2") (pintype "input"))
      (node (ref "U35") (pin "2") (pinfunction "SH/~{LD}_2") (pintype "input"))
      (node (ref "U36") (pin "2") (pinfunction "SH/~{LD}_2") (pintype "input"))
    )
    (net (code "6") (name "/IOIN1") (class "Default")
      (node (ref "P1") (pin "1") (pinfunction "1_1") (pintype "passive"))
      (node (ref "R1") (pin "1") (pinfunction "1_1") (pintype "passive"))
    )
    (net (code "7") (name "/IOIN2") (class "Default")
      (node (ref "P1") (pin "2") (pinfunction "2_2") (pintype "passive"))
      (node (ref "R3") (pin "1") (pinfunction "1_1") (pintype "passive"))
    )
    (net (code "8") (name "/IOIN3") (class "Default")
      (node (ref "P1") (pin "3") (pinfunction "3_3") (pintype "passive"))
      (node (ref "R5") (pin "1") (pinfunction "1_1") (pintype "passive"))
    )
    (net (code "9") (name "/IOIN4") (class "Default")
      (node (ref "P1") (pin "4") (pinfunction "4_4") (pintype "passive"))
      (node (ref "R7") (pin "1") (pinfunction "1_1") (pintype "passive"))
    )
    (net (code "10") (name "/IOIN5") (class "Default")
      (node (ref "P1") (pin "5") (pinfunction "5_5") (pintype "passive"))
      (node (ref "R9") (pin "1") (pinfunction "1_1") (pintype "passive"))
    )
    (net (code "11") (name "/IOIN6") (class "Default")
      (node (ref "P1") (pin "6") (pinfunction "6_6") (pintype "passive"))
      (node (ref "R11") (pin "1") (pinfunction "1_1") (pintype "passive"))
    )
    (net (code "12") (name "/IOIN7") (class "Default")
      (node (ref "P1") (pin "7") (pinfunction "7_7") (pintype "passive"))
      (node (ref "R13") (pin "1") (pinfunction "1_1") (pintype "passive"))
    )
    (net (code "13") (name "/IOIN8") (class "Default")
      (node (ref "P1") (pin "8") (pinfunction "8_8") (pintype "passive"))
      (node (ref "R15") (pin "1") (pinfunction "1_1") (pintype "passive"))
    )
    (net (code "14") (name "/IOIN9") (class "Default")
      (node (ref "P1") (pin "9") (pinfunction "9_9") (pintype "passive"))
      (node (ref "R39") (pin "1") (pinfunction "1_1") (pintype "passive"))
    )
    (net (code "15") (name "/IOIN10") (class "Default")
      (node (ref "P1") (pin "10") (pinfunction "10_10") (pintype "passive"))
      (node (ref "R41") (pin "1") (pinfunction "1_1") (pintype "passive"))
    )
    (net (code "16") (name "/IOIN11") (class "Default")
      (node (ref "P1") (pin "11") (pinfunction "11_11") (pintype "passive"))
      (node (ref "R43") (pin "1") (pinfunction "1_1") (pintype "passive"))
    )
    (net (code "17") (name "/IOIN12") (class "Default")
      (node (ref "P1") (pin "12") (pinfunction "12_12") (pintype "passive"))
      (node (ref "R45") (pin "1") (pinfunction "1_1") (pintype "passive"))
    )
    (net (code "18") (name "/IOIN13") (class "Default")
      (node (ref "P1") (pin "13") (pinfunction "13_13") (pintype "passive"))
      (node (ref "R47") (pin "1") (pinfunction "1_1") (pintype "passive"))
    )
    (net (code "19") (name "/IOIN14") (class "Default")
      (node (ref "P1") (pin "14") (pinfunction "14_14") (pintype "passive"))
      (node (ref "R35") (pin "1") (pinfunction "1_1") (pintype "passive"))
    )
    (net (code "20") (name "/IOIN15") (class "Default")
      (node (ref "P1") (pin "15") (pinfunction "15_15") (pintype "passive"))
      (node (ref "R33") (pin "1") (pinfunction "1_1") (pintype "passive"))
    )
    (net (code "21") (name "/IOIN16") (class "Default")
      (node (ref "P1") (pin "16") (pinfunction "16_16") (pintype "passive"))
      (node (ref "P5") (pin "1") (pinfunction "1_1") (pintype "passive"))
      (node (ref "R37") (pin "1") (pinfunction "1_1") (pintype "passive"))
    )
    (net (code "22") (name "/IOIN17") (class "Default")
      (node (ref "P2") (pin "1") (pinfunction "1_1") (pintype "passive"))
      (node (ref "R73") (pin "1") (pinfunction "1_1") (pintype "passive"))
    )
    (net (code "23") (name "/IOIN18") (class "Default")
      (node (ref "P2") (pin "2") (pinfunction "2_2") (pintype "passive"))
      (node (ref "R67") (pin "1") (pinfunction "1_1") (pintype "passive"))
    )
    (net (code "24") (name "/IOIN19") (class "Default")
      (node (ref "P2") (pin "3") (pinfunction "3_3") (pintype "passive"))
      (node (ref "R75") (pin "1") (pinfunction "1_1") (pintype "passive"))
    )
    (net (code "25") (name "/IOIN20") (class "Default")
      (node (ref "P2") (pin "4") (pinfunction "4_4") (pintype "passive"))
      (node (ref "R79") (pin "1") (pinfunction "1_1") (pintype "passive"))
    )
    (net (code "26") (name "/IOIN21") (class "Default")
      (node (ref "P2") (pin "5") (pinfunction "5_5") (pintype "passive"))
      (node (ref "R77") (pin "1") (pinfunction "1_1") (pintype "passive"))
    )
    (net (code "27") (name "/IOIN22") (class "Default")
      (node (ref "P2") (pin "6") (pinfunction "6_6") (pintype "passive"))
      (node (ref "R69") (pin "1") (pinfunction "1_1") (pintype "passive"))
    )
    (net (code "28") (name "/IOIN23") (class "Default")
      (node (ref "P2") (pin "7") (pinfunction "7_7") (pintype "passive"))
      (node (ref "R71") (pin "1") (pinfunction "1_1") (pintype "passive"))
    )
    (net (code "29") (name "/IOIN24") (class "Default")
      (node (ref "P2") (pin "8") (pinfunction "8_8") (pintype "passive"))
      (node (ref "R65") (pin "1") (pinfunction "1_1") (pintype "passive"))
    )
    (net (code "30") (name "/IOIN25") (class "Default")
      (node (ref "P2") (pin "9") (pinfunction "9_9") (pintype "passive"))
      (node (ref "R105") (pin "1") (pinfunction "1_1") (pintype "passive"))
      (node (ref "R97") (pin "1") (pinfunction "1_1") (pintype "passive"))
    )
    (net (code "31") (name "/IOIN26") (class "Default")
      (node (ref "P2") (pin "10") (pinfunction "10_10") (pintype "passive"))
      (node (ref "R106") (pin "1") (pinfunction "1_1") (pintype "passive"))
      (node (ref "R98") (pin "1") (pinfunction "1_1") (pintype "passive"))
    )
    (net (code "32") (name "/IOIN27") (class "Default")
      (node (ref "P2") (pin "11") (pinfunction "11_11") (pintype "passive"))
      (node (ref "R107") (pin "1") (pinfunction "1_1") (pintype "passive"))
      (node (ref "R99") (pin "1") (pinfunction "1_1") (pintype "passive"))
    )
    (net (code "33") (name "/IOIN28") (class "Default")
      (node (ref "P2") (pin "12") (pinfunction "12_12") (pintype "passive"))
      (node (ref "R100") (pin "1") (pinfunction "1_1") (pintype "passive"))
      (node (ref "R108") (pin "1") (pinfunction "1_1") (pintype "passive"))
    )
    (net (code "34") (name "/IOIN29") (class "Default")
      (node (ref "P2") (pin "13") (pinfunction "13_13") (pintype "passive"))
      (node (ref "R101") (pin "1") (pinfunction "1_1") (pintype "passive"))
      (node (ref "R109") (pin "1") (pinfunction "1_1") (pintype "passive"))
    )
    (net (code "35") (name "/IOIN30") (class "Default")
      (node (ref "P2") (pin "14") (pinfunction "14_14") (pintype "passive"))
      (node (ref "R102") (pin "1") (pinfunction "1_1") (pintype "passive"))
      (node (ref "R110") (pin "1") (pinfunction "1_1") (pintype "passive"))
    )
    (net (code "36") (name "/IOIN31") (class "Default")
      (node (ref "P2") (pin "15") (pinfunction "15_15") (pintype "passive"))
      (node (ref "R103") (pin "1") (pinfunction "1_1") (pintype "passive"))
      (node (ref "R111") (pin "1") (pinfunction "1_1") (pintype "passive"))
    )
    (net (code "37") (name "/IOIN32") (class "Default")
      (node (ref "P2") (pin "16") (pinfunction "16_16") (pintype "passive"))
      (node (ref "R104") (pin "1") (pinfunction "1_1") (pintype "passive"))
      (node (ref "R112") (pin "1") (pinfunction "1_1") (pintype "passive"))
    )
    (net (code "38") (name "/IOIN_1") (class "Default")
      (node (ref "D56") (pin "1") (pinfunction "A_1") (pintype "passive"))
      (node (ref "K5") (pin "4") (pinfunction "4_4") (pintype "passive"))
      (node (ref "P46") (pin "1") (pinfunction "1_1") (pintype "passive"))
      (node (ref "P5") (pin "2") (pinfunction "2_2") (pintype "passive"))
    )
    (net (code "39") (name "/IO_OUT") (class "Default")
      (node (ref "P35") (pin "3") (pinfunction "3_3") (pintype "passive"))
    )
    (net (code "40") (name "/Relay1") (class "Default")
      (node (ref "P35") (pin "4") (pinfunction "4_4") (pintype "passive"))
      (node (ref "R365") (pin "2") (pinfunction "2_2") (pintype "passive"))
    )
    (net (code "41") (name "/_IOIn1") (class "Default")
      (node (ref "R25") (pin "2") (pinfunction "2_2") (pintype "passive"))
      (node (ref "U1") (pin "4") (pinfunction "C_4") (pintype "passive"))
      (node (ref "U33") (pin "6") (pinfunction "H_6") (pintype "input"))
    )
    (net (code "42") (name "/_IOIn2") (class "Default")
      (node (ref "R26") (pin "2") (pinfunction "2_2") (pintype "passive"))
      (node (ref "U2") (pin "4") (pinfunction "C_4") (pintype "passive"))
      (node (ref "U33") (pin "5") (pinfunction "G_5") (pintype "input"))
    )
    (net (code "43") (name "/_IOIn3") (class "Default")
      (node (ref "R27") (pin "2") (pinfunction "2_2") (pintype "passive"))
      (node (ref "U3") (pin "4") (pinfunction "C_4") (pintype "passive"))
      (node (ref "U33") (pin "4") (pinfunction "F_4") (pintype "input"))
    )
    (net (code "44") (name "/_IOIn4") (class "Default")
      (node (ref "R28") (pin "2") (pinfunction "2_2") (pintype "passive"))
      (node (ref "U33") (pin "3") (pinfunction "E_3") (pintype "input"))
      (node (ref "U4") (pin "4") (pinfunction "C_4") (pintype "passive"))
    )
    (net (code "45") (name "/_IOIn5") (class "Default")
      (node (ref "R29") (pin "2") (pinfunction "2_2") (pintype "passive"))
      (node (ref "U33") (pin "14") (pinfunction "D_14") (pintype "input"))
      (node (ref "U5") (pin "4") (pinfunction "C_4") (pintype "passive"))
    )
    (net (code "46") (name "/_IOIn6") (class "Default")
      (node (ref "R30") (pin "2") (pinfunction "2_2") (pintype "passive"))
      (node (ref "U33") (pin "13") (pinfunction "C_13") (pintype "input"))
      (node (ref "U6") (pin "4") (pinfunction "C_4") (pintype "passive"))
    )
    (net (code "47") (name "/_IOIn7") (class "Default")
      (node (ref "R31") (pin "2") (pinfunction "2_2") (pintype "passive"))
      (node (ref "U33") (pin "12") (pinfunction "B_12") (pintype "input"))
      (node (ref "U7") (pin "4") (pinfunction "C_4") (pintype "passive"))
    )
    (net (code "48") (name "/_IOIn8") (class "Default")
      (node (ref "R32") (pin "2") (pinfunction "2_2") (pintype "passive"))
      (node (ref "U33") (pin "11") (pinfunction "A_11") (pintype "input"))
      (node (ref "U8") (pin "4") (pinfunction "C_4") (pintype "passive"))
    )
    (net (code "49") (name "/_IOIn9") (class "Default")
      (node (ref "R60") (pin "2") (pinfunction "2_2") (pintype "passive"))
      (node (ref "U12") (pin "4") (pinfunction "C_4") (pintype "passive"))
      (node (ref "U34") (pin "6") (pinfunction "H_6") (pintype "input"))
    )
    (net (code "50") (name "/_IOIn10") (class "Default")
      (node (ref "R61") (pin "2") (pinfunction "2_2") (pintype "passive"))
      (node (ref "U13") (pin "4") (pinfunction "C_4") (pintype "passive"))
      (node (ref "U34") (pin "5") (pinfunction "G_5") (pintype "input"))
    )
    (net (code "51") (name "/_IOIn11") (class "Default")
      (node (ref "R62") (pin "2") (pinfunction "2_2") (pintype "passive"))
      (node (ref "U14") (pin "4") (pinfunction "C_4") (pintype "passive"))
      (node (ref "U34") (pin "4") (pinfunction "F_4") (pintype "input"))
    )
    (net (code "52") (name "/_IOIn12") (class "Default")
      (node (ref "R63") (pin "2") (pinfunction "2_2") (pintype "passive"))
      (node (ref "U15") (pin "4") (pinfunction "C_4") (pintype "passive"))
      (node (ref "U34") (pin "3") (pinfunction "E_3") (pintype "input"))
    )
    (net (code "53") (name "/_IOIn13") (class "Default")
      (node (ref "R64") (pin "2") (pinfunction "2_2") (pintype "passive"))
      (node (ref "U16") (pin "4") (pinfunction "C_4") (pintype "passive"))
      (node (ref "U34") (pin "14") (pinfunction "D_14") (pintype "input"))
    )
    (net (code "54") (name "/_IOIn14") (class "Default")
      (node (ref "R58") (pin "2") (pinfunction "2_2") (pintype "passive"))
      (node (ref "U10") (pin "4") (pinfunction "C_4") (pintype "passive"))
      (node (ref "U34") (pin "13") (pinfunction "C_13") (pintype "input"))
    )
    (net (code "55") (name "/_IOIn15") (class "Default")
      (node (ref "R57") (pin "2") (pinfunction "2_2") (pintype "passive"))
      (node (ref "U34") (pin "12") (pinfunction "B_12") (pintype "input"))
      (node (ref "U9") (pin "4") (pinfunction "C_4") (pintype "passive"))
    )
    (net (code "56") (name "/_IOIn16") (class "Default")
      (node (ref "R59") (pin "2") (pinfunction "2_2") (pintype "passive"))
      (node (ref "U11") (pin "4") (pinfunction "C_4") (pintype "passive"))
      (node (ref "U34") (pin "11") (pinfunction "A_11") (pintype "input"))
    )
    (net (code "57") (name "/_IOIn17") (class "Default")
      (node (ref "R93") (pin "2") (pinfunction "2_2") (pintype "passive"))
      (node (ref "U21") (pin "4") (pinfunction "C_4") (pintype "passive"))
      (node (ref "U35") (pin "6") (pinfunction "H_6") (pintype "input"))
    )
    (net (code "58") (name "/_IOIn18") (class "Default")
      (node (ref "R90") (pin "2") (pinfunction "2_2") (pintype "passive"))
      (node (ref "U18") (pin "4") (pinfunction "C_4") (pintype "passive"))
      (node (ref "U35") (pin "5") (pinfunction "G_5") (pintype "input"))
    )
    (net (code "59") (name "/_IOIn19") (class "Default")
      (node (ref "R94") (pin "2") (pinfunction "2_2") (pintype "passive"))
      (node (ref "U22") (pin "4") (pinfunction "C_4") (pintype "passive"))
      (node (ref "U35") (pin "4") (pinfunction "F_4") (pintype "input"))
    )
    (net (code "60") (name "/_IOIn20") (class "Default")
      (node (ref "R96") (pin "2") (pinfunction "2_2") (pintype "passive"))
      (node (ref "U24") (pin "4") (pinfunction "C_4") (pintype "passive"))
      (node (ref "U35") (pin "3") (pinfunction "E_3") (pintype "input"))
    )
    (net (code "61") (name "/_IOIn21") (class "Default")
      (node (ref "R95") (pin "2") (pinfunction "2_2") (pintype "passive"))
      (node (ref "U23") (pin "4") (pinfunction "C_4") (pintype "passive"))
      (node (ref "U35") (pin "14") (pinfunction "D_14") (pintype "input"))
    )
    (net (code "62") (name "/_IOIn22") (class "Default")
      (node (ref "R91") (pin "2") (pinfunction "2_2") (pintype "passive"))
      (node (ref "U19") (pin "4") (pinfunction "C_4") (pintype "passive"))
      (node (ref "U35") (pin "13") (pinfunction "C_13") (pintype "input"))
    )
    (net (code "63") (name "/_IOIn23") (class "Default")
      (node (ref "R92") (pin "2") (pinfunction "2_2") (pintype "passive"))
      (node (ref "U20") (pin "4") (pinfunction "C_4") (pintype "passive"))
      (node (ref "U35") (pin "12") (pinfunction "B_12") (pintype "input"))
    )
    (net (code "64") (name "/_IOIn24") (class "Default")
      (node (ref "R89") (pin "2") (pinfunction "2_2") (pintype "passive"))
      (node (ref "U17") (pin "4") (pinfunction "C_4") (pintype "passive"))
      (node (ref "U35") (pin "11") (pinfunction "A_11") (pintype "input"))
    )
    (net (code "65") (name "/_IOIn25") (class "Default")
      (node (ref "R129") (pin "2") (pinfunction "2_2") (pintype "passive"))
      (node (ref "U25") (pin "4") (pinfunction "C_4") (pintype "passive"))
      (node (ref "U36") (pin "6") (pinfunction "H_6") (pintype "input"))
    )
    (net (code "66") (name "/_IOIn26") (class "Default")
      (node (ref "R130") (pin "2") (pinfunction "2_2") (pintype "passive"))
      (node (ref "U26") (pin "4") (pinfunction "C_4") (pintype "passive"))
      (node (ref "U36") (pin "5") (pinfunction "G_5") (pintype "input"))
    )
    (net (code "67") (name "/_IOIn27") (class "Default")
      (node (ref "R131") (pin "2") (pinfunction "2_2") (pintype "passive"))
      (node (ref "U27") (pin "4") (pinfunction "C_4") (pintype "passive"))
      (node (ref "U36") (pin "4") (pinfunction "F_4") (pintype "input"))
    )
    (net (code "68") (name "/_IOIn28") (class "Default")
      (node (ref "R132") (pin "2") (pinfunction "2_2") (pintype "passive"))
      (node (ref "U28") (pin "4") (pinfunction "C_4") (pintype "passive"))
      (node (ref "U36") (pin "3") (pinfunction "E_3") (pintype "input"))
    )
    (net (code "69") (name "/_IOIn29") (class "Default")
      (node (ref "R133") (pin "2") (pinfunction "2_2") (pintype "passive"))
      (node (ref "U29") (pin "4") (pinfunction "C_4") (pintype "passive"))
      (node (ref "U36") (pin "14") (pinfunction "D_14") (pintype "input"))
    )
    (net (code "70") (name "/_IOIn30") (class "Default")
      (node (ref "R134") (pin "2") (pinfunction "2_2") (pintype "passive"))
      (node (ref "U30") (pin "4") (pinfunction "C_4") (pintype "passive"))
      (node (ref "U36") (pin "13") (pinfunction "C_13") (pintype "input"))
    )
    (net (code "71") (name "/_IOIn31") (class "Default")
      (node (ref "R135") (pin "2") (pinfunction "2_2") (pintype "passive"))
      (node (ref "U31") (pin "4") (pinfunction "C_4") (pintype "passive"))
      (node (ref "U36") (pin "12") (pinfunction "B_12") (pintype "input"))
    )
    (net (code "72") (name "/_IOIn32") (class "Default")
      (node (ref "R136") (pin "2") (pinfunction "2_2") (pintype "passive"))
      (node (ref "U32") (pin "4") (pinfunction "C_4") (pintype "passive"))
      (node (ref "U36") (pin "11") (pinfunction "A_11") (pintype "input"))
    )
    (net (code "73") (name "GND") (class "Default")
      (node (ref "C1") (pin "1") (pinfunction "1_1") (pintype "passive"))
      (node (ref "C2") (pin "1") (pinfunction "1_1") (pintype "passive"))
      (node (ref "C3") (pin "1") (pinfunction "1_1") (pintype "passive"))
      (node (ref "C4") (pin "1") (pinfunction "1_1") (pintype "passive"))
      (node (ref "D59") (pin "1") (pinfunction "A_1") (pintype "passive"))
      (node (ref "P13") (pin "4") (pinfunction "4_4") (pintype "passive"))
      (node (ref "P13") (pin "5") (pinfunction "5_5") (pintype "passive"))
      (node (ref "P35") (pin "2") (pinfunction "2_2") (pintype "passive"))
      (node (ref "Q25") (pin "E") (pintype "passive"))
      (node (ref "U1") (pin "3") (pinfunction "E_3") (pintype "passive"))
      (node (ref "U10") (pin "3") (pinfunction "E_3") (pintype "passive"))
      (node (ref "U11") (pin "3") (pinfunction "E_3") (pintype "passive"))
      (node (ref "U12") (pin "3") (pinfunction "E_3") (pintype "passive"))
      (node (ref "U13") (pin "3") (pinfunction "E_3") (pintype "passive"))
      (node (ref "U14") (pin "3") (pinfunction "E_3") (pintype "passive"))
      (node (ref "U15") (pin "3") (pinfunction "E_3") (pintype "passive"))
      (node (ref "U16") (pin "3") (pinfunction "E_3") (pintype "passive"))
      (node (ref "U17") (pin "3") (pinfunction "E_3") (pintype "passive"))
      (node (ref "U18") (pin "3") (pinfunction "E_3") (pintype "passive"))
      (node (ref "U19") (pin "3") (pinfunction "E_3") (pintype "passive"))
      (node (ref "U2") (pin "3") (pinfunction "E_3") (pintype "passive"))
      (node (ref "U20") (pin "3") (pinfunction "E_3") (pintype "passive"))
      (node (ref "U21") (pin "3") (pinfunction "E_3") (pintype "passive"))
      (node (ref "U22") (pin "3") (pinfunction "E_3") (pintype "passive"))
      (node (ref "U23") (pin "3") (pinfunction "E_3") (pintype "passive"))
      (node (ref "U24") (pin "3") (pinfunction "E_3") (pintype "passive"))
      (node (ref "U25") (pin "3") (pinfunction "E_3") (pintype "passive"))
      (node (ref "U26") (pin "3") (pinfunction "E_3") (pintype "passive"))
      (node (ref "U27") (pin "3") (pinfunction "E_3") (pintype "passive"))
      (node (ref "U28") (pin "3") (pinfunction "E_3") (pintype "passive"))
      (node (ref "U29") (pin "3") (pinfunction "E_3") (pintype "passive"))
      (node (ref "U3") (pin "3") (pinfunction "E_3") (pintype "passive"))
      (node (ref "U30") (pin "3") (pinfunction "E_3") (pintype "passive"))
      (node (ref "U31") (pin "3") (pinfunction "E_3") (pintype "passive"))
      (node (ref "U32") (pin "3") (pinfunction "E_3") (pintype "passive"))
      (node (ref "U33") (pin "15") (pinfunction "CLK_INH_15") (pintype "input"))
      (node (ref "U33") (pin "8") (pinfunction "GND_8") (pintype "power_in"))
      (node (ref "U34") (pin "15") (pinfunction "CLK_INH_15") (pintype "input"))
      (node (ref "U34") (pin "8") (pinfunction "GND_8") (pintype "power_in"))
      (node (ref "U35") (pin "15") (pinfunction "CLK_INH_15") (pintype "input"))
      (node (ref "U35") (pin "8") (pinfunction "GND_8") (pintype "power_in"))
      (node (ref "U36") (pin "10") (pinfunction "SER_10") (pintype "power_in"))
      (node (ref "U36") (pin "15") (pinfunction "CLK_INH_15") (pintype "input"))
      (node (ref "U36") (pin "8") (pinfunction "GND_8") (pintype "power_in"))
      (node (ref "U4") (pin "3") (pinfunction "E_3") (pintype "passive"))
      (node (ref "U5") (pin "3") (pinfunction "E_3") (pintype "passive"))
      (node (ref "U6") (pin "3") (pinfunction "E_3") (pintype "passive"))
      (node (ref "U7") (pin "3") (pinfunction "E_3") (pintype "passive"))
      (node (ref "U8") (pin "3") (pinfunction "E_3") (pintype "passive"))
      (node (ref "U9") (pin "3") (pinfunction "E_3") (pintype "passive"))
    )
    (net (code "74") (name "GND_DI") (class "Default")
      (node (ref "F2") (pin "1") (pinfunction "1_1") (pintype "passive"))
      (node (ref "Q1") (pin "3") (pinfunction "S_3") (pintype "input"))
      (node (ref "Q2") (pin "3") (pinfunction "S_3") (pintype "input"))
      (node (ref "Q3") (pin "3") (pinfunction "S_3") (pintype "input"))
      (node (ref "Q4") (pin "3") (pinfunction "S_3") (pintype "input"))
      (node (ref "Q5") (pin "3") (pinfunction "S_3") (pintype "input"))
      (node (ref "Q6") (pin "3") (pinfunction "S_3") (pintype "input"))
      (node (ref "Q7") (pin "3") (pinfunction "S_3") (pintype "input"))
      (node (ref "Q8") (pin "3") (pinfunction "S_3") (pintype "input"))
      (node (ref "R10") (pin "1") (pinfunction "1_1") (pintype "passive"))
      (node (ref "R12") (pin "1") (pinfunction "1_1") (pintype "passive"))
      (node (ref "R121") (pin "1") (pinfunction "1_1") (pintype "passive"))
      (node (ref "R122") (pin "1") (pinfunction "1_1") (pintype "passive"))
      (node (ref "R123") (pin "1") (pinfunction "1_1") (pintype "passive"))
      (node (ref "R124") (pin "1") (pinfunction "1_1") (pintype "passive"))
      (node (ref "R125") (pin "1") (pinfunction "1_1") (pintype "passive"))
      (node (ref "R126") (pin "1") (pinfunction "1_1") (pintype "passive"))
      (node (ref "R127") (pin "1") (pinfunction "1_1") (pintype "passive"))
      (node (ref "R128") (pin "1") (pinfunction "1_1") (pintype "passive"))
      (node (ref "R14") (pin "1") (pinfunction "1_1") (pintype "passive"))
      (node (ref "R16") (pin "1") (pinfunction "1_1") (pintype "passive"))
      (node (ref "R2") (pin "1") (pinfunction "1_1") (pintype "passive"))
      (node (ref "R34") (pin "1") (pinfunction "1_1") (pintype "passive"))
      (node (ref "R36") (pin "1") (pinfunction "1_1") (pintype "passive"))
      (node (ref "R38") (pin "1") (pinfunction "1_1") (pintype "passive"))
      (node (ref "R4") (pin "1") (pinfunction "1_1") (pintype "passive"))
      (node (ref "R40") (pin "1") (pinfunction "1_1") (pintype "passive"))
      (node (ref "R42") (pin "1") (pinfunction "1_1") (pintype "passive"))
      (node (ref "R44") (pin "1") (pinfunction "1_1") (pintype "passive"))
      (node (ref "R46") (pin "1") (pinfunction "1_1") (pintype "passive"))
      (node (ref "R48") (pin "1") (pinfunction "1_1") (pintype "passive"))
      (node (ref "R6") (pin "1") (pinfunction "1_1") (pintype "passive"))
      (node (ref "R66") (pin "1") (pinfunction "1_1") (pintype "passive"))
      (node (ref "R68") (pin "1") (pinfunction "1_1") (pintype "passive"))
      (node (ref "R70") (pin "1") (pinfunction "1_1") (pintype "passive"))
      (node (ref "R72") (pin "1") (pinfunction "1_1") (pintype "passive"))
      (node (ref "R74") (pin "1") (pinfunction "1_1") (pintype "passive"))
      (node (ref "R76") (pin "1") (pinfunction "1_1") (pintype "passive"))
      (node (ref "R78") (pin "1") (pinfunction "1_1") (pintype "passive"))
      (node (ref "R8") (pin "1") (pinfunction "1_1") (pintype "passive"))
      (node (ref "R80") (pin "1") (pinfunction "1_1") (pintype "passive"))
    )
    (net (code "75") (name "GND_DI0") (class "Default")
      (node (ref "K5") (pin "3") (pinfunction "3_3") (pintype "passive"))
      (node (ref "P48") (pin "1") (pinfunction "1_1") (pintype "passive"))
    )
    (net (code "76") (name "Net-(D1-A)") (class "Default")
      (node (ref "D1") (pin "1") (pinfunction "A_1") (pintype "passive"))
      (node (ref "R17") (pin "1") (pinfunction "1_1") (pintype "passive"))
      (node (ref "R2") (pin "2") (pinfunction "2_2") (pintype "passive"))
      (node (ref "U1") (pin "2") (pinfunction "K_2") (pintype "passive"))
    )
    (net (code "77") (name "Net-(D1-K)") (class "Default")
      (node (ref "D1") (pin "2") (pinfunction "K_2") (pintype "passive"))
      (node (ref "LD1") (pin "1") (pinfunction "1_1") (pintype "passive"))
      (node (ref "R1") (pin "2") (pinfunction "2_2") (pintype "passive"))
      (node (ref "R17") (pin "2") (pinfunction "2_2") (pintype "passive"))
    )
    (net (code "78") (name "Net-(D2-A)") (class "Default")
      (node (ref "D2") (pin "1") (pinfunction "A_1") (pintype "passive"))
      (node (ref "R18") (pin "1") (pinfunction "1_1") (pintype "passive"))
      (node (ref "R4") (pin "2") (pinfunction "2_2") (pintype "passive"))
      (node (ref "U2") (pin "2") (pinfunction "K_2") (pintype "passive"))
    )
    (net (code "79") (name "Net-(D2-K)") (class "Default")
      (node (ref "D2") (pin "2") (pinfunction "K_2") (pintype "passive"))
      (node (ref "LD2") (pin "1") (pinfunction "1_1") (pintype "passive"))
      (node (ref "R18") (pin "2") (pinfunction "2_2") (pintype "passive"))
      (node (ref "R3") (pin "2") (pinfunction "2_2") (pintype "passive"))
    )
    (net (code "80") (name "Net-(D3-A)") (class "Default")
      (node (ref "D3") (pin "1") (pinfunction "A_1") (pintype "passive"))
      (node (ref "R19") (pin "1") (pinfunction "1_1") (pintype "passive"))
      (node (ref "R6") (pin "2") (pinfunction "2_2") (pintype "passive"))
      (node (ref "U3") (pin "2") (pinfunction "K_2") (pintype "passive"))
    )
    (net (code "81") (name "Net-(D3-K)") (class "Default")
      (node (ref "D3") (pin "2") (pinfunction "K_2") (pintype "passive"))
      (node (ref "LD4") (pin "1") (pinfunction "1_1") (pintype "passive"))
      (node (ref "R19") (pin "2") (pinfunction "2_2") (pintype "passive"))
      (node (ref "R5") (pin "2") (pinfunction "2_2") (pintype "passive"))
    )
    (net (code "82") (name "Net-(D4-A)") (class "Default")
      (node (ref "D4") (pin "1") (pinfunction "A_1") (pintype "passive"))
      (node (ref "R20") (pin "1") (pinfunction "1_1") (pintype "passive"))
      (node (ref "R8") (pin "2") (pinfunction "2_2") (pintype "passive"))
      (node (ref "U4") (pin "2") (pinfunction "K_2") (pintype "passive"))
    )
    (net (code "83") (name "Net-(D4-K)") (class "Default")
      (node (ref "D4") (pin "2") (pinfunction "K_2") (pintype "passive"))
      (node (ref "LD5") (pin "1") (pinfunction "1_1") (pintype "passive"))
      (node (ref "R20") (pin "2") (pinfunction "2_2") (pintype "passive"))
      (node (ref "R7") (pin "2") (pinfunction "2_2") (pintype "passive"))
    )
    (net (code "84") (name "Net-(D5-A)") (class "Default")
      (node (ref "D5") (pin "1") (pinfunction "A_1") (pintype "passive"))
      (node (ref "R10") (pin "2") (pinfunction "2_2") (pintype "passive"))
      (node (ref "R21") (pin "1") (pinfunction "1_1") (pintype "passive"))
      (node (ref "U5") (pin "2") (pinfunction "K_2") (pintype "passive"))
    )
    (net (code "85") (name "Net-(D5-K)") (class "Default")
      (node (ref "D5") (pin "2") (pinfunction "K_2") (pintype "passive"))
      (node (ref "LD6") (pin "1") (pinfunction "1_1") (pintype "passive"))
      (node (ref "R21") (pin "2") (pinfunction "2_2") (pintype "passive"))
      (node (ref "R9") (pin "2") (pinfunction "2_2") (pintype "passive"))
    )
    (net (code "86") (name "Net-(D6-A)") (class "Default")
      (node (ref "D6") (pin "1") (pinfunction "A_1") (pintype "passive"))
      (node (ref "R12") (pin "2") (pinfunction "2_2") (pintype "passive"))
      (node (ref "R22") (pin "1") (pinfunction "1_1") (pintype "passive"))
      (node (ref "U6") (pin "2") (pinfunction "K_2") (pintype "passive"))
    )
    (net (code "87") (name "Net-(D6-K)") (class "Default")
      (node (ref "D6") (pin "2") (pinfunction "K_2") (pintype "passive"))
      (node (ref "LD3") (pin "1") (pinfunction "1_1") (pintype "passive"))
      (node (ref "R11") (pin "2") (pinfunction "2_2") (pintype "passive"))
      (node (ref "R22") (pin "2") (pinfunction "2_2") (pintype "passive"))
    )
    (net (code "88") (name "Net-(D7-A)") (class "Default")
      (node (ref "D7") (pin "1") (pinfunction "A_1") (pintype "passive"))
      (node (ref "R14") (pin "2") (pinfunction "2_2") (pintype "passive"))
      (node (ref "R23") (pin "1") (pinfunction "1_1") (pintype "passive"))
      (node (ref "U7") (pin "2") (pinfunction "K_2") (pintype "passive"))
    )
    (net (code "89") (name "Net-(D7-K)") (class "Default")
      (node (ref "D7") (pin "2") (pinfunction "K_2") (pintype "passive"))
      (node (ref "LD7") (pin "1") (pinfunction "1_1") (pintype "passive"))
      (node (ref "R13") (pin "2") (pinfunction "2_2") (pintype "passive"))
      (node (ref "R23") (pin "2") (pinfunction "2_2") (pintype "passive"))
    )
    (net (code "90") (name "Net-(D8-A)") (class "Default")
      (node (ref "D8") (pin "1") (pinfunction "A_1") (pintype "passive"))
      (node (ref "R16") (pin "2") (pinfunction "2_2") (pintype "passive"))
      (node (ref "R24") (pin "1") (pinfunction "1_1") (pintype "passive"))
      (node (ref "U8") (pin "2") (pinfunction "K_2") (pintype "passive"))
    )
    (net (code "91") (name "Net-(D8-K)") (class "Default")
      (node (ref "D8") (pin "2") (pinfunction "K_2") (pintype "passive"))
      (node (ref "LD8") (pin "1") (pinfunction "1_1") (pintype "passive"))
      (node (ref "R15") (pin "2") (pinfunction "2_2") (pintype "passive"))
      (node (ref "R24") (pin "2") (pinfunction "2_2") (pintype "passive"))
    )
    (net (code "92") (name "Net-(D9-A)") (class "Default")
      (node (ref "D9") (pin "1") (pinfunction "A_1") (pintype "passive"))
      (node (ref "R34") (pin "2") (pinfunction "2_2") (pintype "passive"))
      (node (ref "R49") (pin "1") (pinfunction "1_1") (pintype "passive"))
      (node (ref "U9") (pin "2") (pinfunction "K_2") (pintype "passive"))
    )
    (net (code "93") (name "Net-(D9-K)") (class "Default")
      (node (ref "D9") (pin "2") (pinfunction "K_2") (pintype "passive"))
      (node (ref "LD9") (pin "1") (pinfunction "1_1") (pintype "passive"))
      (node (ref "R33") (pin "2") (pinfunction "2_2") (pintype "passive"))
      (node (ref "R49") (pin "2") (pinfunction "2_2") (pintype "passive"))
    )
    (net (code "94") (name "Net-(D10-A)") (class "Default")
      (node (ref "D10") (pin "1") (pinfunction "A_1") (pintype "passive"))
      (node (ref "R36") (pin "2") (pinfunction "2_2") (pintype "passive"))
      (node (ref "R50") (pin "1") (pinfunction "1_1") (pintype "passive"))
      (node (ref "U10") (pin "2") (pinfunction "K_2") (pintype "passive"))
    )
    (net (code "95") (name "Net-(D10-K)") (class "Default")
      (node (ref "D10") (pin "2") (pinfunction "K_2") (pintype "passive"))
      (node (ref "LD10") (pin "1") (pinfunction "1_1") (pintype "passive"))
      (node (ref "R35") (pin "2") (pinfunction "2_2") (pintype "passive"))
      (node (ref "R50") (pin "2") (pinfunction "2_2") (pintype "passive"))
    )
    (net (code "96") (name "Net-(D11-A)") (class "Default")
      (node (ref "D11") (pin "1") (pinfunction "A_1") (pintype "passive"))
      (node (ref "R38") (pin "2") (pinfunction "2_2") (pintype "passive"))
      (node (ref "R51") (pin "1") (pinfunction "1_1") (pintype "passive"))
      (node (ref "U11") (pin "2") (pinfunction "K_2") (pintype "passive"))
    )
    (net (code "97") (name "Net-(D11-K)") (class "Default")
      (node (ref "D11") (pin "2") (pinfunction "K_2") (pintype "passive"))
      (node (ref "LD11") (pin "1") (pinfunction "1_1") (pintype "passive"))
      (node (ref "R37") (pin "2") (pinfunction "2_2") (pintype "passive"))
      (node (ref "R51") (pin "2") (pinfunction "2_2") (pintype "passive"))
    )
    (net (code "98") (name "Net-(D12-A)") (class "Default")
      (node (ref "D12") (pin "1") (pinfunction "A_1") (pintype "passive"))
      (node (ref "R40") (pin "2") (pinfunction "2_2") (pintype "passive"))
      (node (ref "R52") (pin "1") (pinfunction "1_1") (pintype "passive"))
      (node (ref "U12") (pin "2") (pinfunction "K_2") (pintype "passive"))
    )
    (net (code "99") (name "Net-(D12-K)") (class "Default")
      (node (ref "D12") (pin "2") (pinfunction "K_2") (pintype "passive"))
      (node (ref "LD12") (pin "1") (pinfunction "1_1") (pintype "passive"))
      (node (ref "R39") (pin "2") (pinfunction "2_2") (pintype "passive"))
      (node (ref "R52") (pin "2") (pinfunction "2_2") (pintype "passive"))
    )
    (net (code "100") (name "Net-(D13-A)") (class "Default")
      (node (ref "D13") (pin "1") (pinfunction "A_1") (pintype "passive"))
      (node (ref "R42") (pin "2") (pinfunction "2_2") (pintype "passive"))
      (node (ref "R53") (pin "1") (pinfunction "1_1") (pintype "passive"))
      (node (ref "U13") (pin "2") (pinfunction "K_2") (pintype "passive"))
    )
    (net (code "101") (name "Net-(D13-K)") (class "Default")
      (node (ref "D13") (pin "2") (pinfunction "K_2") (pintype "passive"))
      (node (ref "LD13") (pin "1") (pinfunction "1_1") (pintype "passive"))
      (node (ref "R41") (pin "2") (pinfunction "2_2") (pintype "passive"))
      (node (ref "R53") (pin "2") (pinfunction "2_2") (pintype "passive"))
    )
    (net (code "102") (name "Net-(D14-A)") (class "Default")
      (node (ref "D14") (pin "1") (pinfunction "A_1") (pintype "passive"))
      (node (ref "R44") (pin "2") (pinfunction "2_2") (pintype "passive"))
      (node (ref "R54") (pin "1") (pinfunction "1_1") (pintype "passive"))
      (node (ref "U14") (pin "2") (pinfunction "K_2") (pintype "passive"))
    )
    (net (code "103") (name "Net-(D14-K)") (class "Default")
      (node (ref "D14") (pin "2") (pinfunction "K_2") (pintype "passive"))
      (node (ref "LD14") (pin "1") (pinfunction "1_1") (pintype "passive"))
      (node (ref "R43") (pin "2") (pinfunction "2_2") (pintype "passive"))
      (node (ref "R54") (pin "2") (pinfunction "2_2") (pintype "passive"))
    )
    (net (code "104") (name "Net-(D15-A)") (class "Default")
      (node (ref "D15") (pin "1") (pinfunction "A_1") (pintype "passive"))
      (node (ref "R46") (pin "2") (pinfunction "2_2") (pintype "passive"))
      (node (ref "R55") (pin "1") (pinfunction "1_1") (pintype "passive"))
      (node (ref "U15") (pin "2") (pinfunction "K_2") (pintype "passive"))
    )
    (net (code "105") (name "Net-(D15-K)") (class "Default")
      (node (ref "D15") (pin "2") (pinfunction "K_2") (pintype "passive"))
      (node (ref "LD15") (pin "1") (pinfunction "1_1") (pintype "passive"))
      (node (ref "R45") (pin "2") (pinfunction "2_2") (pintype "passive"))
      (node (ref "R55") (pin "2") (pinfunction "2_2") (pintype "passive"))
    )
    (net (code "106") (name "Net-(D16-A)") (class "Default")
      (node (ref "D16") (pin "1") (pinfunction "A_1") (pintype "passive"))
      (node (ref "R48") (pin "2") (pinfunction "2_2") (pintype "passive"))
      (node (ref "R56") (pin "1") (pinfunction "1_1") (pintype "passive"))
      (node (ref "U16") (pin "2") (pinfunction "K_2") (pintype "passive"))
    )
    (net (code "107") (name "Net-(D16-K)") (class "Default")
      (node (ref "D16") (pin "2") (pinfunction "K_2") (pintype "passive"))
      (node (ref "LD16") (pin "1") (pinfunction "1_1") (pintype "passive"))
      (node (ref "R47") (pin "2") (pinfunction "2_2") (pintype "passive"))
      (node (ref "R56") (pin "2") (pinfunction "2_2") (pintype "passive"))
    )
    (net (code "108") (name "Net-(D17-A)") (class "Default")
      (node (ref "D17") (pin "1") (pinfunction "A_1") (pintype "passive"))
      (node (ref "R66") (pin "2") (pinfunction "2_2") (pintype "passive"))
      (node (ref "R81") (pin "1") (pinfunction "1_1") (pintype "passive"))
      (node (ref "U17") (pin "2") (pinfunction "K_2") (pintype "passive"))
    )
    (net (code "109") (name "Net-(D17-K)") (class "Default")
      (node (ref "D17") (pin "2") (pinfunction "K_2") (pintype "passive"))
      (node (ref "LD17") (pin "1") (pinfunction "1_1") (pintype "passive"))
      (node (ref "R65") (pin "2") (pinfunction "2_2") (pintype "passive"))
      (node (ref "R81") (pin "2") (pinfunction "2_2") (pintype "passive"))
    )
    (net (code "110") (name "Net-(D18-A)") (class "Default")
      (node (ref "D18") (pin "1") (pinfunction "A_1") (pintype "passive"))
      (node (ref "R68") (pin "2") (pinfunction "2_2") (pintype "passive"))
      (node (ref "R82") (pin "1") (pinfunction "1_1") (pintype "passive"))
      (node (ref "U18") (pin "2") (pinfunction "K_2") (pintype "passive"))
    )
    (net (code "111") (name "Net-(D18-K)") (class "Default")
      (node (ref "D18") (pin "2") (pinfunction "K_2") (pintype "passive"))
      (node (ref "LD18") (pin "1") (pinfunction "1_1") (pintype "passive"))
      (node (ref "R67") (pin "2") (pinfunction "2_2") (pintype "passive"))
      (node (ref "R82") (pin "2") (pinfunction "2_2") (pintype "passive"))
    )
    (net (code "112") (name "Net-(D19-A)") (class "Default")
      (node (ref "D19") (pin "1") (pinfunction "A_1") (pintype "passive"))
      (node (ref "R70") (pin "2") (pinfunction "2_2") (pintype "passive"))
      (node (ref "R83") (pin "1") (pinfunction "1_1") (pintype "passive"))
      (node (ref "U19") (pin "2") (pinfunction "K_2") (pintype "passive"))
    )
    (net (code "113") (name "Net-(D19-K)") (class "Default")
      (node (ref "D19") (pin "2") (pinfunction "K_2") (pintype "passive"))
      (node (ref "LD19") (pin "1") (pinfunction "1_1") (pintype "passive"))
      (node (ref "R69") (pin "2") (pinfunction "2_2") (pintype "passive"))
      (node (ref "R83") (pin "2") (pinfunction "2_2") (pintype "passive"))
    )
    (net (code "114") (name "Net-(D20-A)") (class "Default")
      (node (ref "D20") (pin "1") (pinfunction "A_1") (pintype "passive"))
      (node (ref "R72") (pin "2") (pinfunction "2_2") (pintype "passive"))
      (node (ref "R84") (pin "1") (pinfunction "1_1") (pintype "passive"))
      (node (ref "U20") (pin "2") (pinfunction "K_2") (pintype "passive"))
    )
    (net (code "115") (name "Net-(D20-K)") (class "Default")
      (node (ref "D20") (pin "2") (pinfunction "K_2") (pintype "passive"))
      (node (ref "LD20") (pin "1") (pinfunction "1_1") (pintype "passive"))
      (node (ref "R71") (pin "2") (pinfunction "2_2") (pintype "passive"))
      (node (ref "R84") (pin "2") (pinfunction "2_2") (pintype "passive"))
    )
    (net (code "116") (name "Net-(D21-A)") (class "Default")
      (node (ref "D21") (pin "1") (pinfunction "A_1") (pintype "passive"))
      (node (ref "R74") (pin "2") (pinfunction "2_2") (pintype "passive"))
      (node (ref "R85") (pin "1") (pinfunction "1_1") (pintype "passive"))
      (node (ref "U21") (pin "2") (pinfunction "K_2") (pintype "passive"))
    )
    (net (code "117") (name "Net-(D21-K)") (class "Default")
      (node (ref "D21") (pin "2") (pinfunction "K_2") (pintype "passive"))
      (node (ref "LD21") (pin "1") (pinfunction "1_1") (pintype "passive"))
      (node (ref "R73") (pin "2") (pinfunction "2_2") (pintype "passive"))
      (node (ref "R85") (pin "2") (pinfunction "2_2") (pintype "passive"))
    )
    (net (code "118") (name "Net-(D22-A)") (class "Default")
      (node (ref "D22") (pin "1") (pinfunction "A_1") (pintype "passive"))
      (node (ref "R76") (pin "2") (pinfunction "2_2") (pintype "passive"))
      (node (ref "R86") (pin "1") (pinfunction "1_1") (pintype "passive"))
      (node (ref "U22") (pin "2") (pinfunction "K_2") (pintype "passive"))
    )
    (net (code "119") (name "Net-(D22-K)") (class "Default")
      (node (ref "D22") (pin "2") (pinfunction "K_2") (pintype "passive"))
      (node (ref "LD22") (pin "1") (pinfunction "1_1") (pintype "passive"))
      (node (ref "R75") (pin "2") (pinfunction "2_2") (pintype "passive"))
      (node (ref "R86") (pin "2") (pinfunction "2_2") (pintype "passive"))
    )
    (net (code "120") (name "Net-(D23-A)") (class "Default")
      (node (ref "D23") (pin "1") (pinfunction "A_1") (pintype "passive"))
      (node (ref "R78") (pin "2") (pinfunction "2_2") (pintype "passive"))
      (node (ref "R87") (pin "1") (pinfunction "1_1") (pintype "passive"))
      (node (ref "U23") (pin "2") (pinfunction "K_2") (pintype "passive"))
    )
    (net (code "121") (name "Net-(D23-K)") (class "Default")
      (node (ref "D23") (pin "2") (pinfunction "K_2") (pintype "passive"))
      (node (ref "LD23") (pin "1") (pinfunction "1_1") (pintype "passive"))
      (node (ref "R77") (pin "2") (pinfunction "2_2") (pintype "passive"))
      (node (ref "R87") (pin "2") (pinfunction "2_2") (pintype "passive"))
    )
    (net (code "122") (name "Net-(D24-A)") (class "Default")
      (node (ref "D24") (pin "1") (pinfunction "A_1") (pintype "passive"))
      (node (ref "R80") (pin "2") (pinfunction "2_2") (pintype "passive"))
      (node (ref "R88") (pin "1") (pinfunction "1_1") (pintype "passive"))
      (node (ref "U24") (pin "2") (pinfunction "K_2") (pintype "passive"))
    )
    (net (code "123") (name "Net-(D24-K)") (class "Default")
      (node (ref "D24") (pin "2") (pinfunction "K_2") (pintype "passive"))
      (node (ref "LD24") (pin "1") (pinfunction "1_1") (pintype "passive"))
      (node (ref "R79") (pin "2") (pinfunction "2_2") (pintype "passive"))
      (node (ref "R88") (pin "2") (pinfunction "2_2") (pintype "passive"))
    )
    (net (code "124") (name "Net-(D57-A)") (class "Default")
      (node (ref "D57") (pin "1") (pinfunction "A_1") (pintype "passive"))
      (node (ref "K5") (pin "2") (pinfunction "2_2") (pintype "passive"))
      (node (ref "Q25") (pin "C") (pintype "passive"))
    )
    (net (code "125") (name "Net-(F1-Pad2)") (class "Default")
      (node (ref "F1") (pin "2") (pinfunction "2_2") (pintype "passive"))
      (node (ref "P3") (pin "1") (pinfunction "1_1") (pintype "passive"))
      (node (ref "P3") (pin "2") (pinfunction "2_2") (pintype "passive"))
    )
    (net (code "126") (name "Net-(F2-Pad2)") (class "Default")
      (node (ref "F2") (pin "2") (pinfunction "2_2") (pintype "passive"))
      (node (ref "P3") (pin "5") (pinfunction "5_5") (pintype "passive"))
      (node (ref "P3") (pin "6") (pinfunction "6_6") (pintype "passive"))
    )
    (net (code "127") (name "Net-(LD25-Pad1)") (class "Default")
      (node (ref "LD25") (pin "1") (pinfunction "1_1") (pintype "passive"))
      (node (ref "R113") (pin "2") (pinfunction "2_2") (pintype "passive"))
    )
    (net (code "128") (name "Net-(LD26-Pad1)") (class "Default")
      (node (ref "LD26") (pin "1") (pinfunction "1_1") (pintype "passive"))
      (node (ref "R114") (pin "2") (pinfunction "2_2") (pintype "passive"))
    )
    (net (code "129") (name "Net-(LD27-Pad1)") (class "Default")
      (node (ref "LD27") (pin "1") (pinfunction "1_1") (pintype "passive"))
      (node (ref "R119") (pin "2") (pinfunction "2_2") (pintype "passive"))
    )
    (net (code "130") (name "Net-(LD28-Pad1)") (class "Default")
      (node (ref "LD28") (pin "1") (pinfunction "1_1") (pintype "passive"))
      (node (ref "R115") (pin "2") (pinfunction "2_2") (pintype "passive"))
    )
    (net (code "131") (name "Net-(LD29-Pad1)") (class "Default")
      (node (ref "LD29") (pin "1") (pinfunction "1_1") (pintype "passive"))
      (node (ref "R116") (pin "2") (pinfunction "2_2") (pintype "passive"))
    )
    (net (code "132") (name "Net-(LD30-Pad1)") (class "Default")
      (node (ref "LD30") (pin "1") (pinfunction "1_1") (pintype "passive"))
      (node (ref "R120") (pin "2") (pinfunction "2_2") (pintype "passive"))
    )
    (net (code "133") (name "Net-(LD31-Pad1)") (class "Default")
      (node (ref "LD31") (pin "1") (pinfunction "1_1") (pintype "passive"))
      (node (ref "R117") (pin "2") (pinfunction "2_2") (pintype "passive"))
    )
    (net (code "134") (name "Net-(LD32-Pad1)") (class "Default")
      (node (ref "LD32") (pin "1") (pinfunction "1_1") (pintype "passive"))
      (node (ref "R118") (pin "2") (pinfunction "2_2") (pintype "passive"))
    )
    (net (code "135") (name "Net-(Q1-D)") (class "Default")
      (node (ref "Q1") (pin "2") (pinfunction "D_2") (pintype "input"))
      (node (ref "U25") (pin "2") (pinfunction "K_2") (pintype "passive"))
    )
    (net (code "136") (name "Net-(Q1-G)") (class "Default")
      (node (ref "Q1") (pin "1") (pinfunction "G_1") (pintype "input"))
      (node (ref "R105") (pin "2") (pinfunction "2_2") (pintype "passive"))
      (node (ref "R121") (pin "2") (pinfunction "2_2") (pintype "passive"))
    )
    (net (code "137") (name "Net-(Q2-D)") (class "Default")
      (node (ref "Q2") (pin "2") (pinfunction "D_2") (pintype "input"))
      (node (ref "U26") (pin "2") (pinfunction "K_2") (pintype "passive"))
    )
    (net (code "138") (name "Net-(Q2-G)") (class "Default")
      (node (ref "Q2") (pin "1") (pinfunction "G_1") (pintype "input"))
      (node (ref "R106") (pin "2") (pinfunction "2_2") (pintype "passive"))
      (node (ref "R122") (pin "2") (pinfunction "2_2") (pintype "passive"))
    )
    (net (code "139") (name "Net-(Q3-D)") (class "Default")
      (node (ref "Q3") (pin "2") (pinfunction "D_2") (pintype "input"))
      (node (ref "U27") (pin "2") (pinfunction "K_2") (pintype "passive"))
    )
    (net (code "140") (name "Net-(Q3-G)") (class "Default")
      (node (ref "Q3") (pin "1") (pinfunction "G_1") (pintype "input"))
      (node (ref "R107") (pin "2") (pinfunction "2_2") (pintype "passive"))
      (node (ref "R123") (pin "2") (pinfunction "2_2") (pintype "passive"))
    )
    (net (code "141") (name "Net-(Q4-D)") (class "Default")
      (node (ref "Q4") (pin "2") (pinfunction "D_2") (pintype "input"))
      (node (ref "U28") (pin "2") (pinfunction "K_2") (pintype "passive"))
    )
    (net (code "142") (name "Net-(Q4-G)") (class "Default")
      (node (ref "Q4") (pin "1") (pinfunction "G_1") (pintype "input"))
      (node (ref "R108") (pin "2") (pinfunction "2_2") (pintype "passive"))
      (node (ref "R124") (pin "2") (pinfunction "2_2") (pintype "passive"))
    )
    (net (code "143") (name "Net-(Q5-D)") (class "Default")
      (node (ref "Q5") (pin "2") (pinfunction "D_2") (pintype "input"))
      (node (ref "U29") (pin "2") (pinfunction "K_2") (pintype "passive"))
    )
    (net (code "144") (name "Net-(Q5-G)") (class "Default")
      (node (ref "Q5") (pin "1") (pinfunction "G_1") (pintype "input"))
      (node (ref "R109") (pin "2") (pinfunction "2_2") (pintype "passive"))
      (node (ref "R125") (pin "2") (pinfunction "2_2") (pintype "passive"))
    )
    (net (code "145") (name "Net-(Q6-D)") (class "Default")
      (node (ref "Q6") (pin "2") (pinfunction "D_2") (pintype "input"))
      (node (ref "U30") (pin "2") (pinfunction "K_2") (pintype "passive"))
    )
    (net (code "146") (name "Net-(Q6-G)") (class "Default")
      (node (ref "Q6") (pin "1") (pinfunction "G_1") (pintype "input"))
      (node (ref "R110") (pin "2") (pinfunction "2_2") (pintype "passive"))
      (node (ref "R126") (pin "2") (pinfunction "2_2") (pintype "passive"))
    )
    (net (code "147") (name "Net-(Q7-D)") (class "Default")
      (node (ref "Q7") (pin "2") (pinfunction "D_2") (pintype "input"))
      (node (ref "U31") (pin "2") (pinfunction "K_2") (pintype "passive"))
    )
    (net (code "148") (name "Net-(Q7-G)") (class "Default")
      (node (ref "Q7") (pin "1") (pinfunction "G_1") (pintype "input"))
      (node (ref "R111") (pin "2") (pinfunction "2_2") (pintype "passive"))
      (node (ref "R127") (pin "2") (pinfunction "2_2") (pintype "passive"))
    )
    (net (code "149") (name "Net-(Q8-D)") (class "Default")
      (node (ref "Q8") (pin "2") (pinfunction "D_2") (pintype "input"))
      (node (ref "U32") (pin "2") (pinfunction "K_2") (pintype "passive"))
    )
    (net (code "150") (name "Net-(Q8-G)") (class "Default")
      (node (ref "Q8") (pin "1") (pinfunction "G_1") (pintype "input"))
      (node (ref "R112") (pin "2") (pinfunction "2_2") (pintype "passive"))
      (node (ref "R128") (pin "2") (pinfunction "2_2") (pintype "passive"))
    )
    (net (code "151") (name "Net-(Q25-PadB)") (class "Default")
      (node (ref "Q25") (pin "B") (pintype "passive"))
      (node (ref "R365") (pin "1") (pinfunction "1_1") (pintype "passive"))
    )
    (net (code "152") (name "Net-(U1-A)") (class "Default")
      (node (ref "LD1") (pin "2") (pinfunction "2_2") (pintype "passive"))
      (node (ref "U1") (pin "1") (pinfunction "A_1") (pintype "passive"))
    )
    (net (code "153") (name "Net-(U2-A)") (class "Default")
      (node (ref "LD2") (pin "2") (pinfunction "2_2") (pintype "passive"))
      (node (ref "U2") (pin "1") (pinfunction "A_1") (pintype "passive"))
    )
    (net (code "154") (name "Net-(U3-A)") (class "Default")
      (node (ref "LD4") (pin "2") (pinfunction "2_2") (pintype "passive"))
      (node (ref "U3") (pin "1") (pinfunction "A_1") (pintype "passive"))
    )
    (net (code "155") (name "Net-(U4-A)") (class "Default")
      (node (ref "LD5") (pin "2") (pinfunction "2_2") (pintype "passive"))
      (node (ref "U4") (pin "1") (pinfunction "A_1") (pintype "passive"))
    )
    (net (code "156") (name "Net-(U5-A)") (class "Default")
      (node (ref "LD6") (pin "2") (pinfunction "2_2") (pintype "passive"))
      (node (ref "U5") (pin "1") (pinfunction "A_1") (pintype "passive"))
    )
    (net (code "157") (name "Net-(U6-A)") (class "Default")
      (node (ref "LD3") (pin "2") (pinfunction "2_2") (pintype "passive"))
      (node (ref "U6") (pin "1") (pinfunction "A_1") (pintype "passive"))
    )
    (net (code "158") (name "Net-(U7-A)") (class "Default")
      (node (ref "LD7") (pin "2") (pinfunction "2_2") (pintype "passive"))
      (node (ref "U7") (pin "1") (pinfunction "A_1") (pintype "passive"))
    )
    (net (code "159") (name "Net-(U8-A)") (class "Default")
      (node (ref "LD8") (pin "2") (pinfunction "2_2") (pintype "passive"))
      (node (ref "U8") (pin "1") (pinfunction "A_1") (pintype "passive"))
    )
    (net (code "160") (name "Net-(U9-A)") (class "Default")
      (node (ref "LD9") (pin "2") (pinfunction "2_2") (pintype "passive"))
      (node (ref "U9") (pin "1") (pinfunction "A_1") (pintype "passive"))
    )
    (net (code "161") (name "Net-(U10-A)") (class "Default")
      (node (ref "LD10") (pin "2") (pinfunction "2_2") (pintype "passive"))
      (node (ref "U10") (pin "1") (pinfunction "A_1") (pintype "passive"))
    )
    (net (code "162") (name "Net-(U11-A)") (class "Default")
      (node (ref "LD11") (pin "2") (pinfunction "2_2") (pintype "passive"))
      (node (ref "U11") (pin "1") (pinfunction "A_1") (pintype "passive"))
    )
    (net (code "163") (name "Net-(U12-A)") (class "Default")
      (node (ref "LD12") (pin "2") (pinfunction "2_2") (pintype "passive"))
      (node (ref "U12") (pin "1") (pinfunction "A_1") (pintype "passive"))
    )
    (net (code "164") (name "Net-(U13-A)") (class "Default")
      (node (ref "LD13") (pin "2") (pinfunction "2_2") (pintype "passive"))
      (node (ref "U13") (pin "1") (pinfunction "A_1") (pintype "passive"))
    )
    (net (code "165") (name "Net-(U14-A)") (class "Default")
      (node (ref "LD14") (pin "2") (pinfunction "2_2") (pintype "passive"))
      (node (ref "U14") (pin "1") (pinfunction "A_1") (pintype "passive"))
    )
    (net (code "166") (name "Net-(U15-A)") (class "Default")
      (node (ref "LD15") (pin "2") (pinfunction "2_2") (pintype "passive"))
      (node (ref "U15") (pin "1") (pinfunction "A_1") (pintype "passive"))
    )
    (net (code "167") (name "Net-(U16-A)") (class "Default")
      (node (ref "LD16") (pin "2") (pinfunction "2_2") (pintype "passive"))
      (node (ref "U16") (pin "1") (pinfunction "A_1") (pintype "passive"))
    )
    (net (code "168") (name "Net-(U17-A)") (class "Default")
      (node (ref "LD17") (pin "2") (pinfunction "2_2") (pintype "passive"))
      (node (ref "U17") (pin "1") (pinfunction "A_1") (pintype "passive"))
    )
    (net (code "169") (name "Net-(U18-A)") (class "Default")
      (node (ref "LD18") (pin "2") (pinfunction "2_2") (pintype "passive"))
      (node (ref "U18") (pin "1") (pinfunction "A_1") (pintype "passive"))
    )
    (net (code "170") (name "Net-(U19-A)") (class "Default")
      (node (ref "LD19") (pin "2") (pinfunction "2_2") (pintype "passive"))
      (node (ref "U19") (pin "1") (pinfunction "A_1") (pintype "passive"))
    )
    (net (code "171") (name "Net-(U20-A)") (class "Default")
      (node (ref "LD20") (pin "2") (pinfunction "2_2") (pintype "passive"))
      (node (ref "U20") (pin "1") (pinfunction "A_1") (pintype "passive"))
    )
    (net (code "172") (name "Net-(U21-A)") (class "Default")
      (node (ref "LD21") (pin "2") (pinfunction "2_2") (pintype "passive"))
      (node (ref "U21") (pin "1") (pinfunction "A_1") (pintype "passive"))
    )
    (net (code "173") (name "Net-(U22-A)") (class "Default")
      (node (ref "LD22") (pin "2") (pinfunction "2_2") (pintype "passive"))
      (node (ref "U22") (pin "1") (pinfunction "A_1") (pintype "passive"))
    )
    (net (code "174") (name "Net-(U23-A)") (class "Default")
      (node (ref "LD23") (pin "2") (pinfunction "2_2") (pintype "passive"))
      (node (ref "U23") (pin "1") (pinfunction "A_1") (pintype "passive"))
    )
    (net (code "175") (name "Net-(U24-A)") (class "Default")
      (node (ref "LD24") (pin "2") (pinfunction "2_2") (pintype "passive"))
      (node (ref "U24") (pin "1") (pinfunction "A_1") (pintype "passive"))
    )
    (net (code "176") (name "Net-(U25-A)") (class "Default")
      (node (ref "LD25") (pin "2") (pinfunction "2_2") (pintype "passive"))
      (node (ref "U25") (pin "1") (pinfunction "A_1") (pintype "passive"))
    )
    (net (code "177") (name "Net-(U26-A)") (class "Default")
      (node (ref "LD26") (pin "2") (pinfunction "2_2") (pintype "passive"))
      (node (ref "U26") (pin "1") (pinfunction "A_1") (pintype "passive"))
    )
    (net (code "178") (name "Net-(U27-A)") (class "Default")
      (node (ref "LD27") (pin "2") (pinfunction "2_2") (pintype "passive"))
      (node (ref "U27") (pin "1") (pinfunction "A_1") (pintype "passive"))
    )
    (net (code "179") (name "Net-(U28-A)") (class "Default")
      (node (ref "LD28") (pin "2") (pinfunction "2_2") (pintype "passive"))
      (node (ref "U28") (pin "1") (pinfunction "A_1") (pintype "passive"))
    )
    (net (code "180") (name "Net-(U29-A)") (class "Default")
      (node (ref "LD29") (pin "2") (pinfunction "2_2") (pintype "passive"))
      (node (ref "U29") (pin "1") (pinfunction "A_1") (pintype "passive"))
    )
    (net (code "181") (name "Net-(U30-A)") (class "Default")
      (node (ref "LD30") (pin "2") (pinfunction "2_2") (pintype "passive"))
      (node (ref "U30") (pin "1") (pinfunction "A_1") (pintype "passive"))
    )
    (net (code "182") (name "Net-(U31-A)") (class "Default")
      (node (ref "LD31") (pin "2") (pinfunction "2_2") (pintype "passive"))
      (node (ref "U31") (pin "1") (pinfunction "A_1") (pintype "passive"))
    )
    (net (code "183") (name "Net-(U32-A)") (class "Default")
      (node (ref "LD32") (pin "2") (pinfunction "2_2") (pintype "passive"))
      (node (ref "U32") (pin "1") (pinfunction "A_1") (pintype "passive"))
    )
    (net (code "184") (name "Net-(U33-SER)") (class "Default")
      (node (ref "R206") (pin "1") (pinfunction "1_1") (pintype "passive"))
      (node (ref "U33") (pin "10") (pinfunction "SER_10") (pintype "power_in"))
      (node (ref "U34") (pin "9") (pinfunction "QH_9") (pintype "output"))
    )
    (net (code "185") (name "Net-(U34-SER)") (class "Default")
      (node (ref "R206") (pin "2") (pinfunction "2_2") (pintype "passive"))
      (node (ref "R207") (pin "1") (pinfunction "1_1") (pintype "passive"))
      (node (ref "U34") (pin "10") (pinfunction "SER_10") (pintype "power_in"))
      (node (ref "U35") (pin "9") (pinfunction "QH_9") (pintype "output"))
    )
    (net (code "186") (name "Net-(U35-SER)") (class "Default")
      (node (ref "R207") (pin "2") (pinfunction "2_2") (pintype "passive"))
      (node (ref "U35") (pin "10") (pinfunction "SER_10") (pintype "power_in"))
      (node (ref "U36") (pin "9") (pinfunction "QH_9") (pintype "output"))
    )
    (net (code "187") (name "VCC_DI") (class "Default")
      (node (ref "F1") (pin "1") (pinfunction "1_1") (pintype "passive"))
      (node (ref "R100") (pin "2") (pinfunction "2_2") (pintype "passive"))
      (node (ref "R101") (pin "2") (pinfunction "2_2") (pintype "passive"))
      (node (ref "R102") (pin "2") (pinfunction "2_2") (pintype "passive"))
      (node (ref "R103") (pin "2") (pinfunction "2_2") (pintype "passive"))
      (node (ref "R104") (pin "2") (pinfunction "2_2") (pintype "passive"))
      (node (ref "R113") (pin "1") (pinfunction "1_1") (pintype "passive"))
      (node (ref "R114") (pin "1") (pinfunction "1_1") (pintype "passive"))
      (node (ref "R115") (pin "1") (pinfunction "1_1") (pintype "passive"))
      (node (ref "R116") (pin "1") (pinfunction "1_1") (pintype "passive"))
      (node (ref "R117") (pin "1") (pinfunction "1_1") (pintype "passive"))
      (node (ref "R118") (pin "1") (pinfunction "1_1") (pintype "passive"))
      (node (ref "R119") (pin "1") (pinfunction "1_1") (pintype "passive"))
      (node (ref "R120") (pin "1") (pinfunction "1_1") (pintype "passive"))
      (node (ref "R97") (pin "2") (pinfunction "2_2") (pintype "passive"))
      (node (ref "R98") (pin "2") (pinfunction "2_2") (pintype "passive"))
      (node (ref "R99") (pin "2") (pinfunction "2_2") (pintype "passive"))
    )
    (net (code "188") (name "VCC_DI0") (class "Default")
      (node (ref "D56") (pin "2") (pinfunction "K_2") (pintype "passive"))
      (node (ref "P45") (pin "1") (pinfunction "1_1") (pintype "passive"))
      (node (ref "P47") (pin "1") (pinfunction "1_1") (pintype "passive"))
    )
    (net (code "189") (name "unconnected-(K5-Pad5)") (class "Default")
      (node (ref "K5") (pin "5") (pinfunction "5_5") (pintype "passive"))
    )
    (net (code "190") (name "unconnected-(P3-Pad3)") (class "Default")
      (node (ref "P3") (pin "3") (pinfunction "3_3") (pintype "passive"))
    )
    (net (code "191") (name "unconnected-(P3-Pad4)") (class "Default")
      (node (ref "P3") (pin "4") (pinfunction "4_4") (pintype "passive"))
    )
    (net (code "192") (name "unconnected-(U33-QH-Pad9)") (class "Default")
      (node (ref "U33") (pin "9") (pinfunction "QH_9") (pintype "output"))
    )
    (net (code "193") (name "unconnected-(U34-~{QH}-Pad7)") (class "Default")
      (node (ref "U34") (pin "7") (pinfunction "~{QH}_7") (pintype "output"))
    )
    (net (code "194") (name "unconnected-(U35-~{QH}-Pad7)") (class "Default")
      (node (ref "U35") (pin "7") (pinfunction "~{QH}_7") (pintype "output"))
    )
    (net (code "195") (name "unconnected-(U36-~{QH}-Pad7)") (class "Default")
      (node (ref "U36") (pin "7") (pinfunction "~{QH}_7") (pintype "output"))
    )
  )
)
